# EEZ_PSU_power_board_r5B8.net
KiCad netlist of a schematic drawn in EAGLE
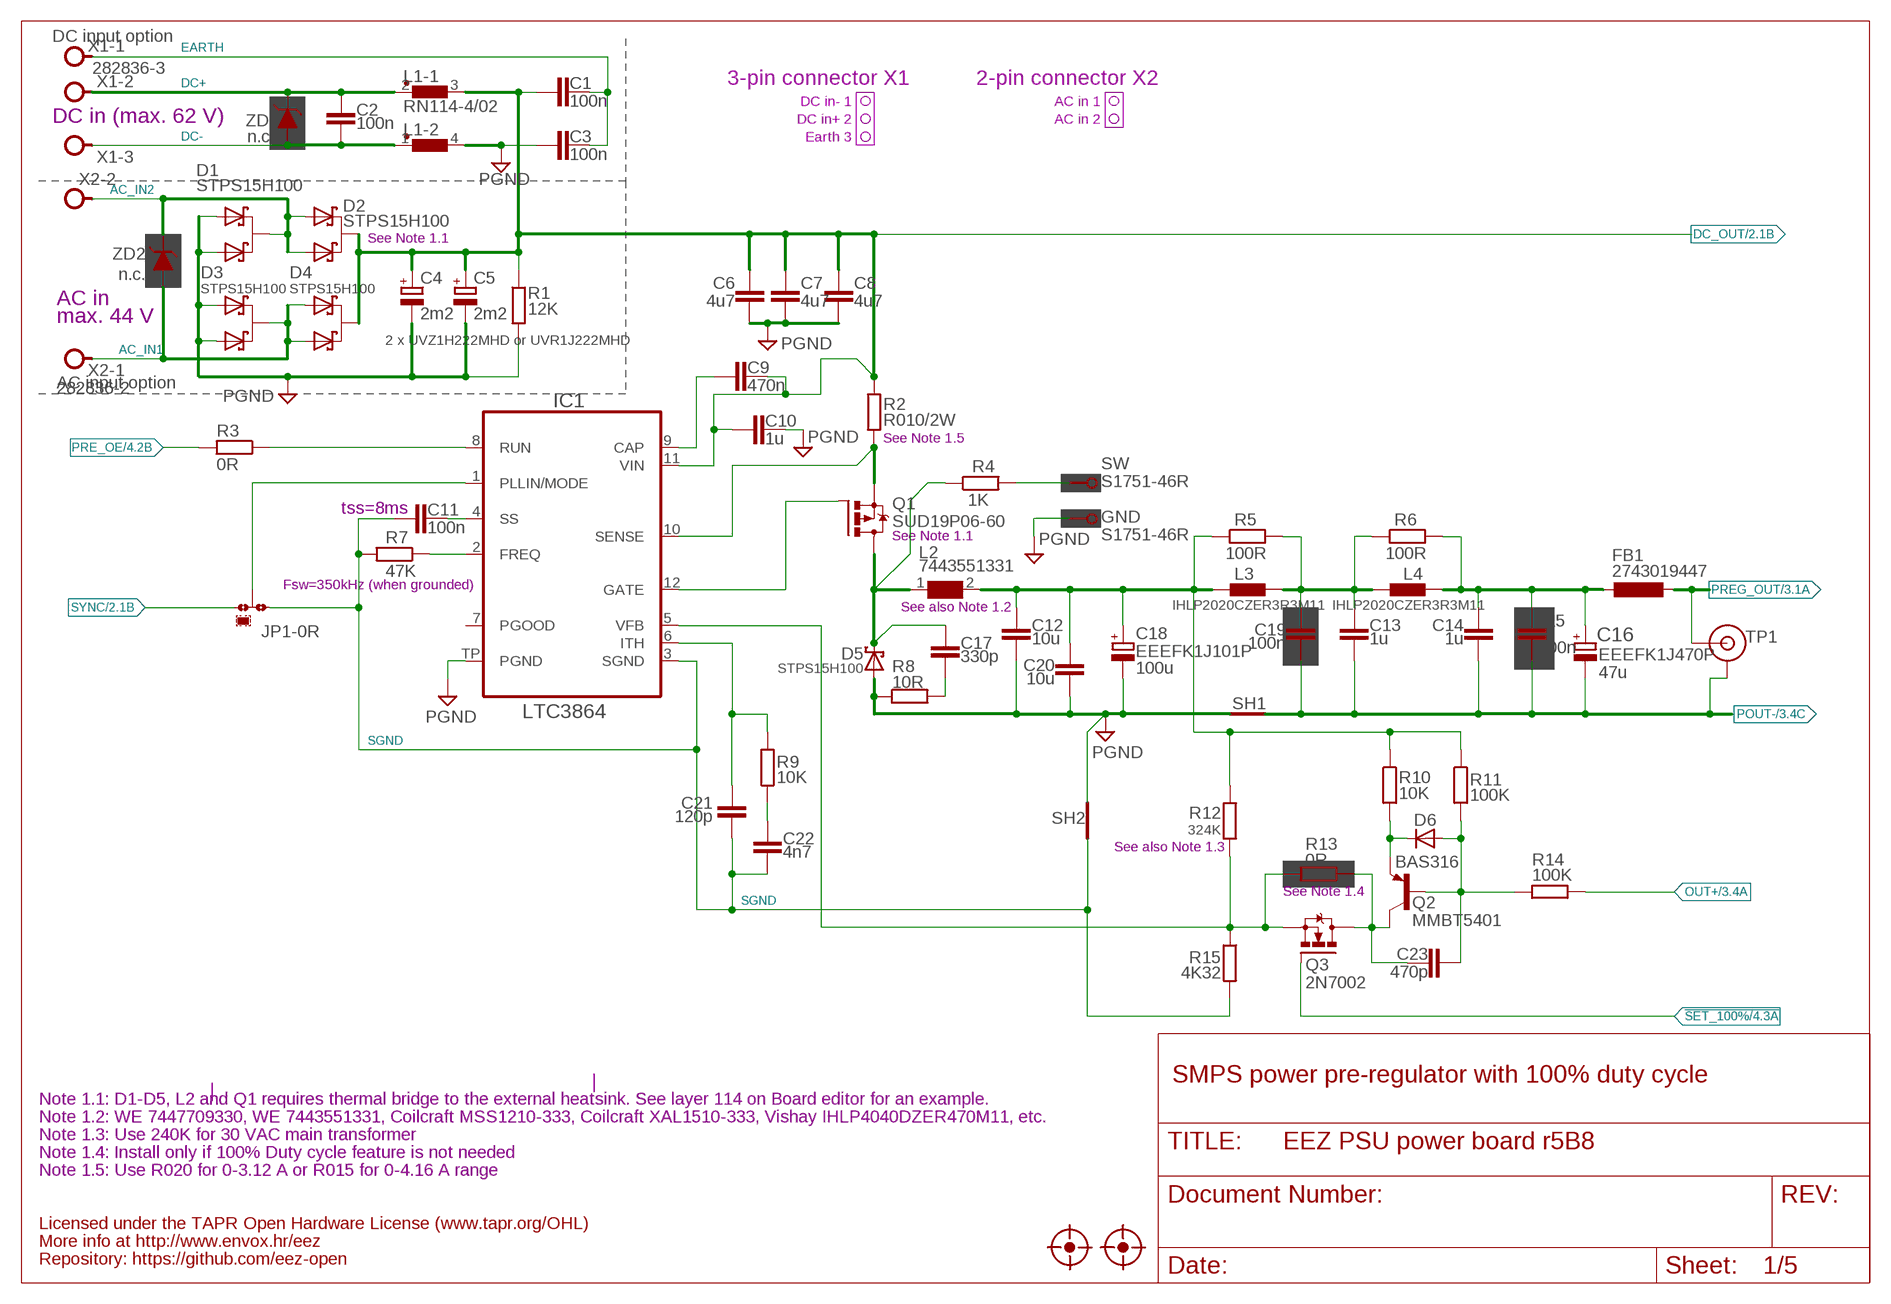
[diagram p0: schematic, sheet 1]
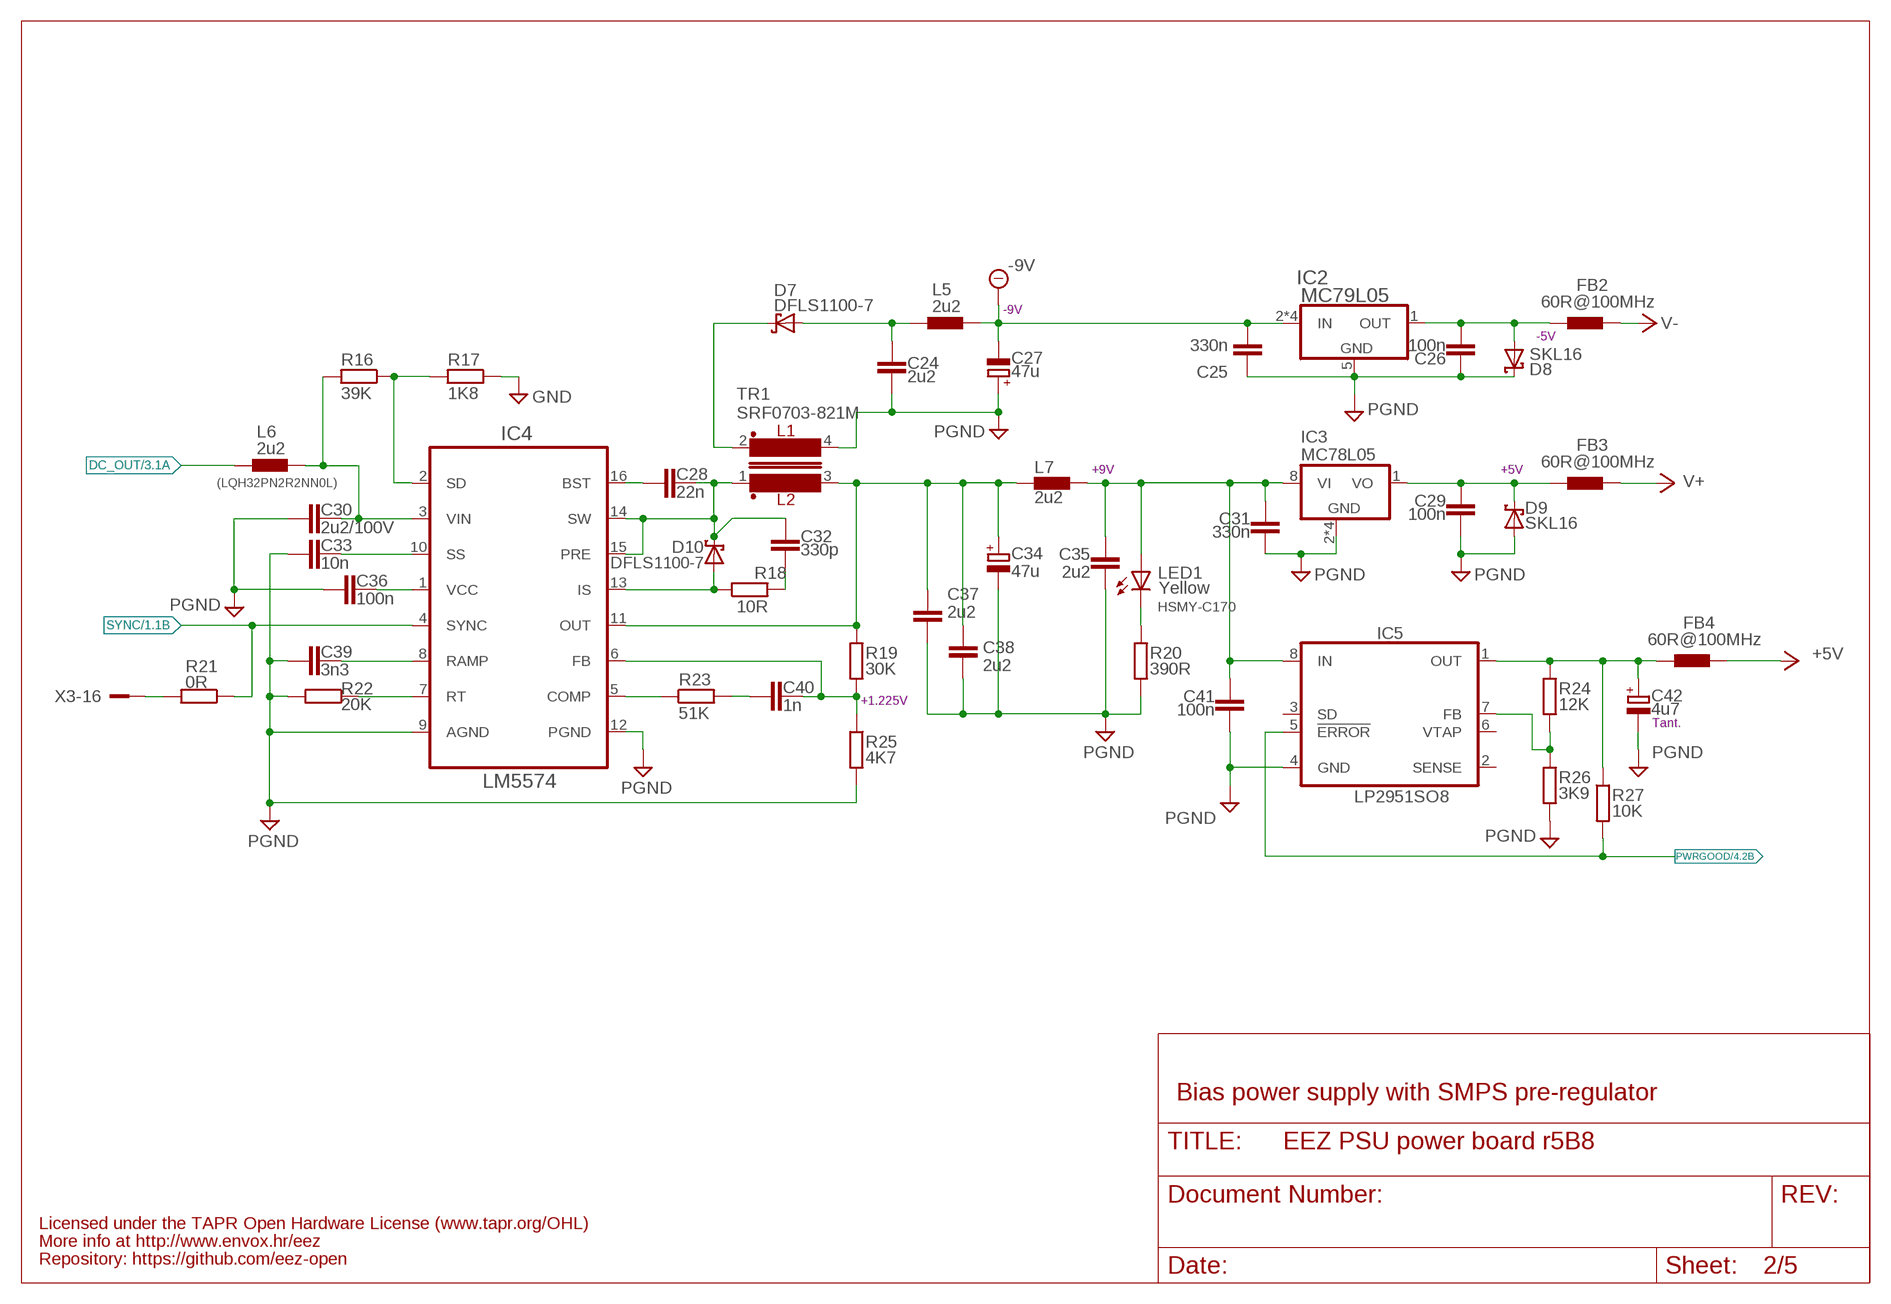
[diagram p1: schematic, sheet 2]
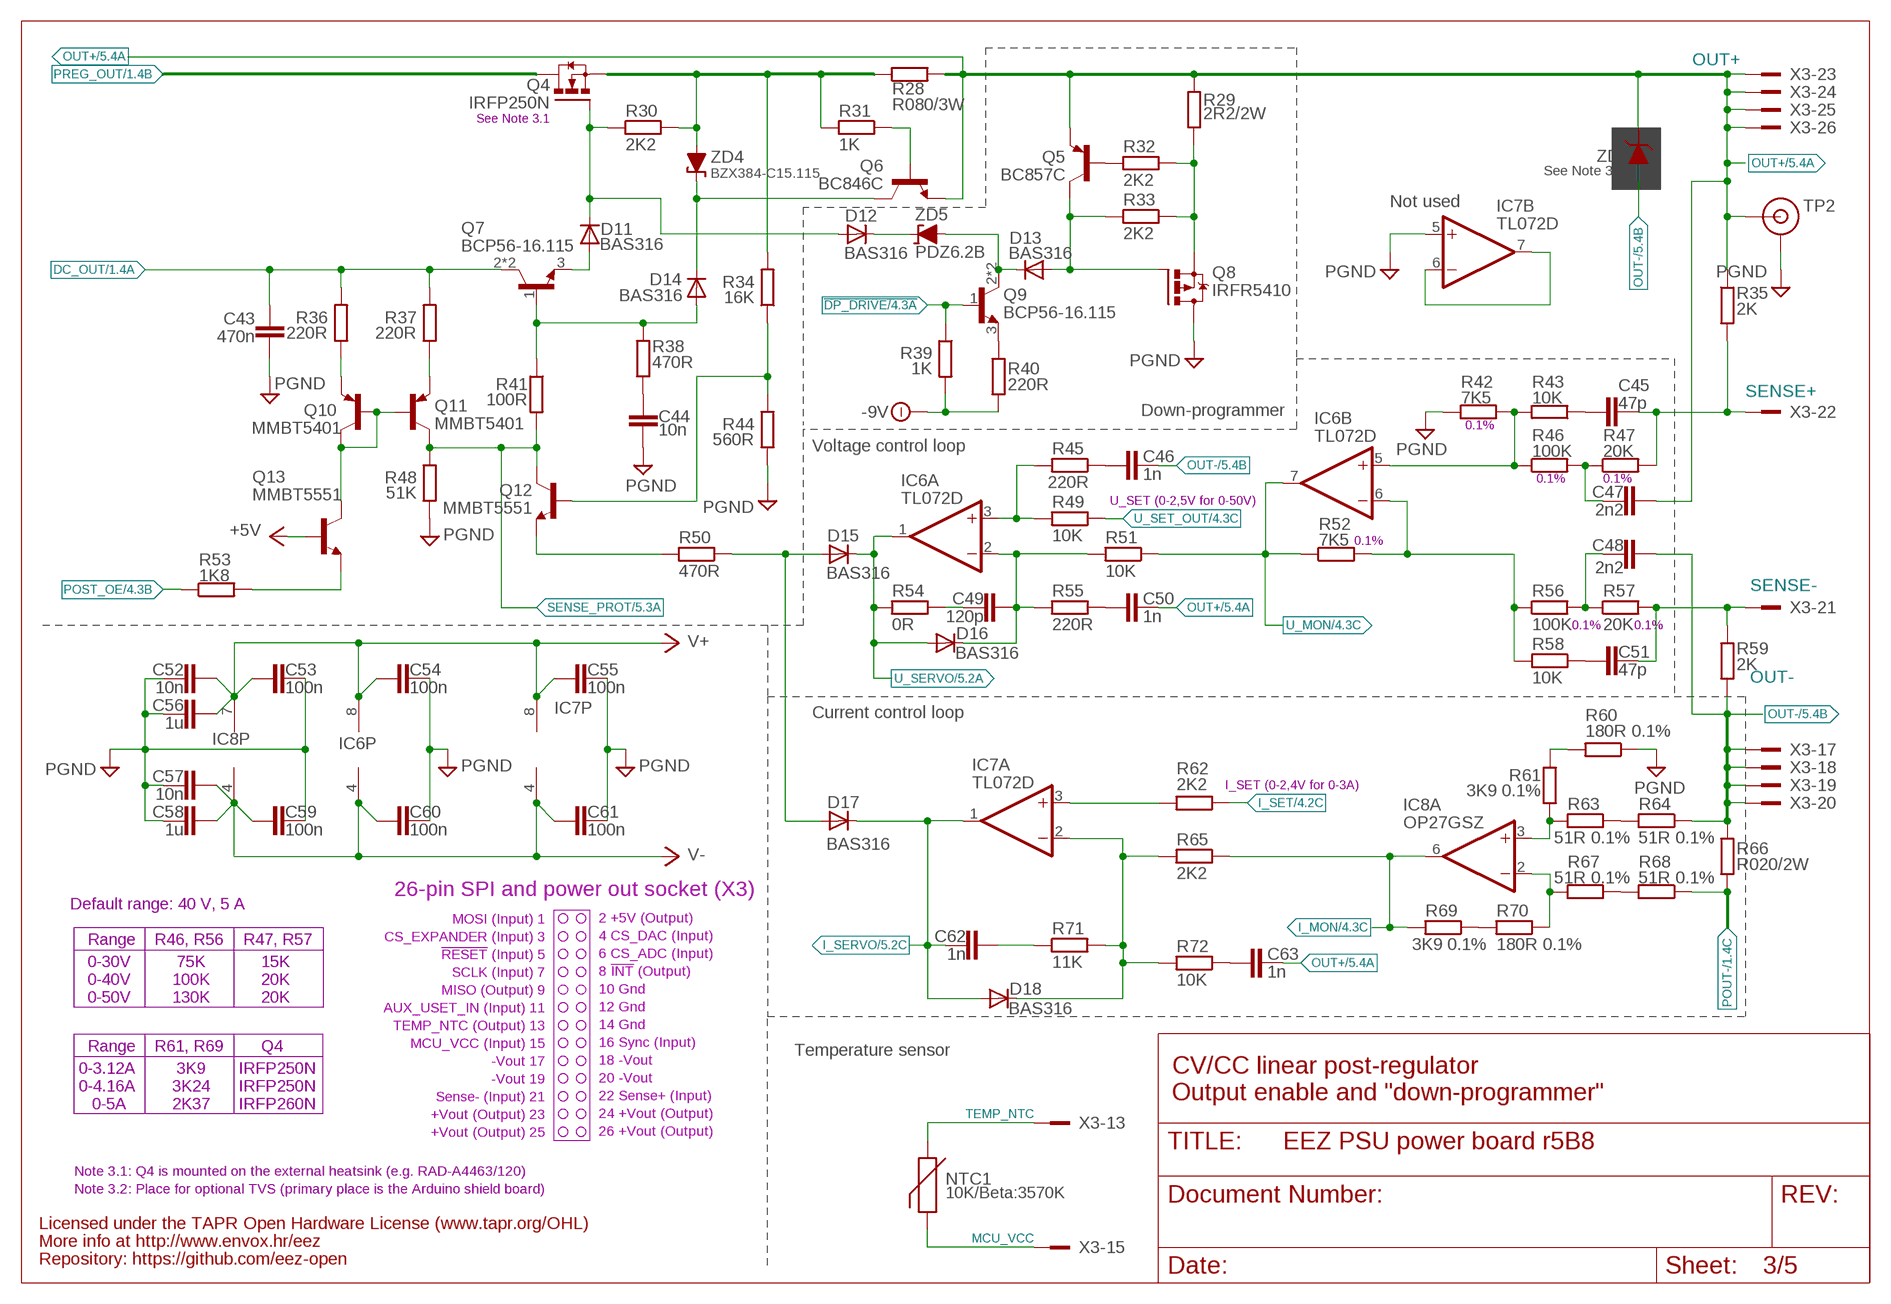
[diagram p2: schematic, sheet 3]
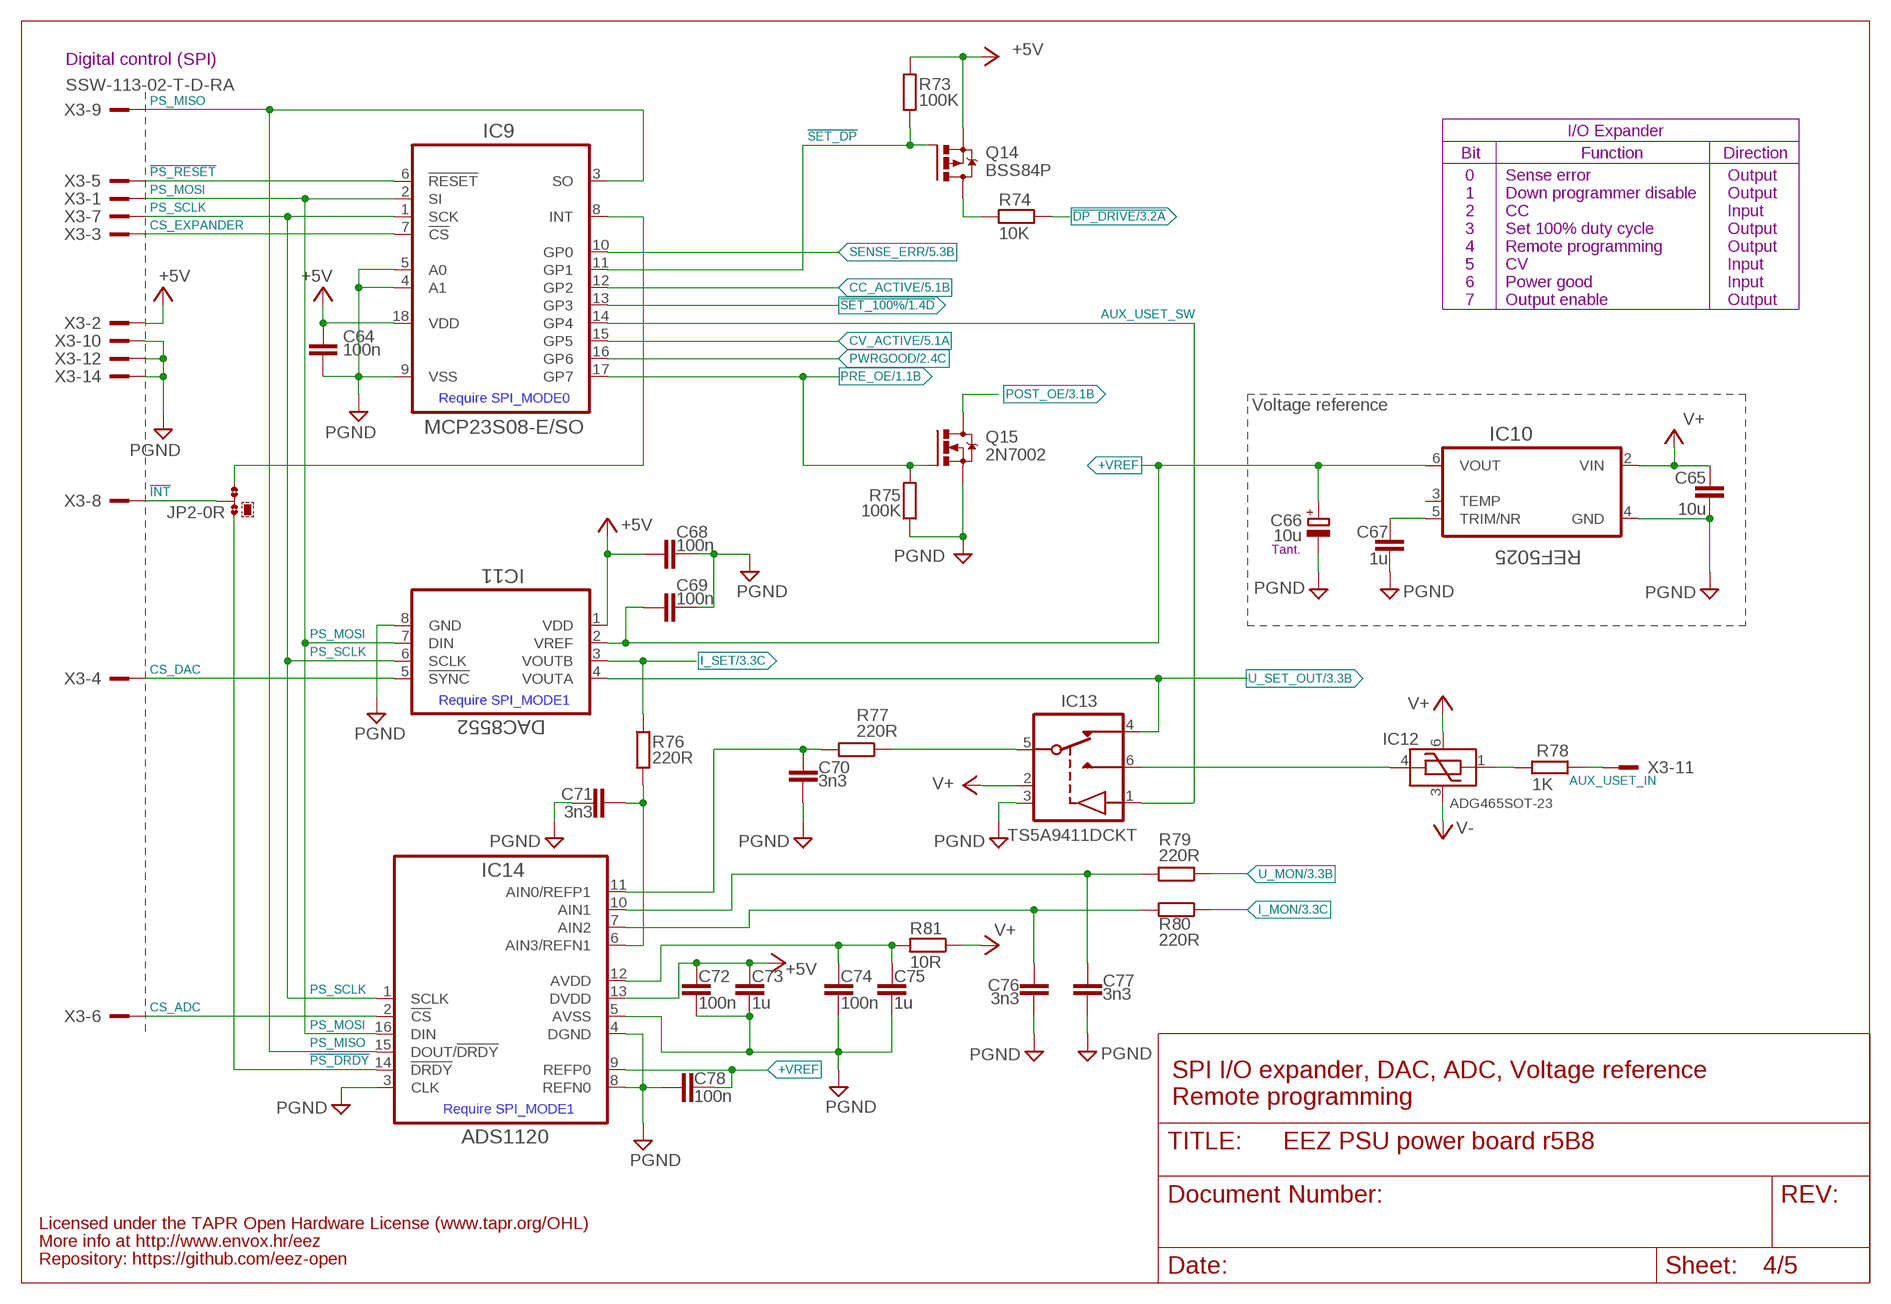
[diagram p3: schematic, sheet 4]
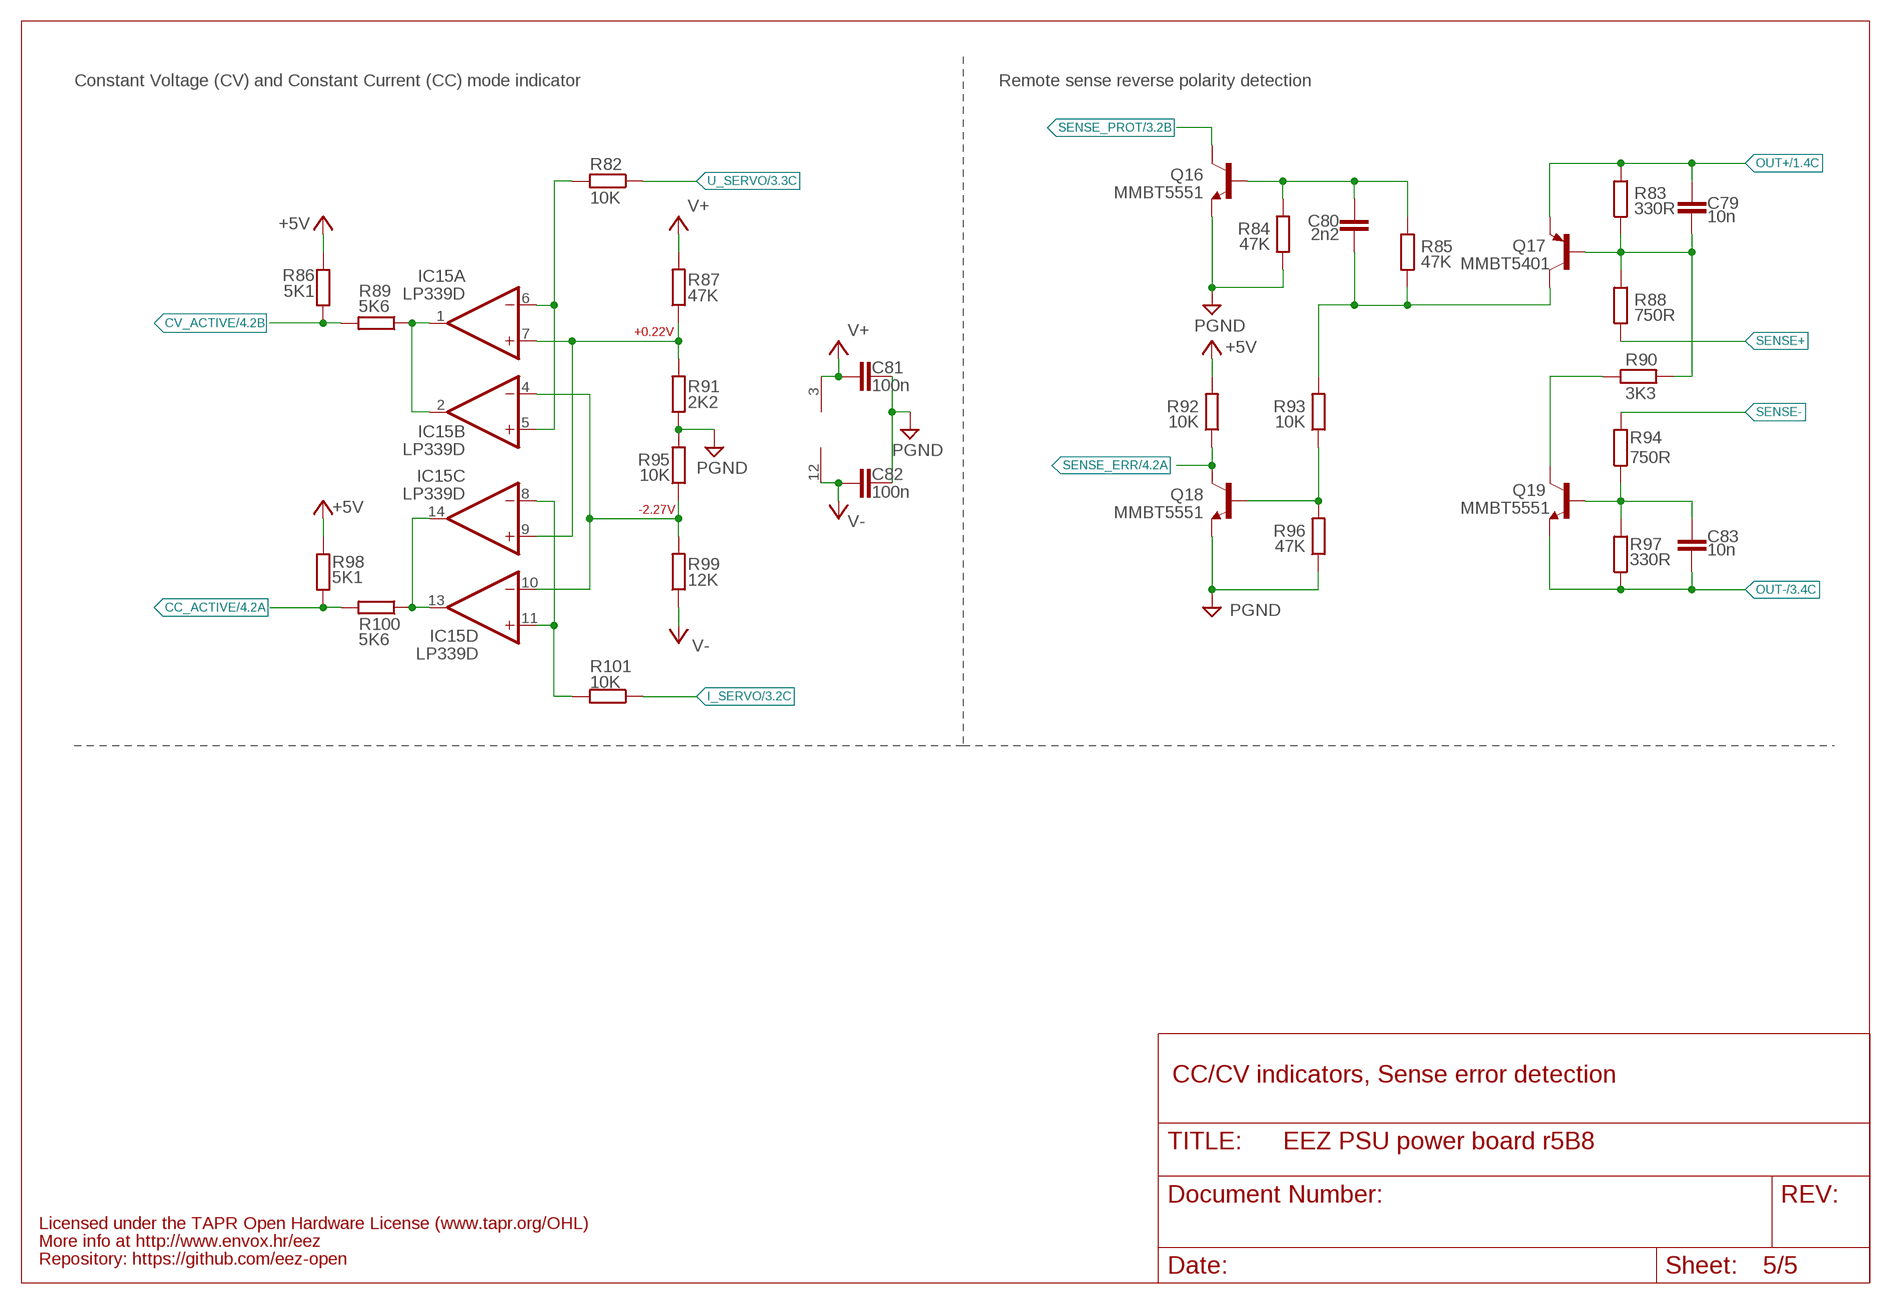
[diagram p4: schematic, sheet 5]

(export (version "E")
  (design (tool "Eeschema 10.0.6"))
  (components
    (comp (ref "C24")
      (value "2u2")
      (footprint "eagle-import:C0805")
      (libsource (lib "eagle-import") (part "C-EUC0805"))
    )
    (comp (ref "C25")
      (value "330n")
      (footprint "eagle-import:C0805")
      (libsource (lib "eagle-import") (part "C-EUC0805"))
    )
    (comp (ref "C26")
      (value "100n")
      (footprint "eagle-import:C0805")
      (libsource (lib "eagle-import") (part "C-EUC0805"))
    )
    (comp (ref "C27")
      (value "47u")
      (footprint "eagle-import:CAPAE660X610N")
      (libsource (lib "eagle-import") (part "ECAPPANASONIC_H"))
    )
    (comp (ref "C28")
      (value "22n")
      (footprint "eagle-import:C0805")
      (libsource (lib "eagle-import") (part "C-EUC0805"))
    )
    (comp (ref "C29")
      (value "100n")
      (footprint "eagle-import:C0805")
      (libsource (lib "eagle-import") (part "C-EUC0805"))
    )
    (comp (ref "C30")
      (value "2u2/100V")
      (footprint "eagle-import:C1210")
      (libsource (lib "eagle-import") (part "C-EUC1210"))
    )
    (comp (ref "C31")
      (value "330n")
      (footprint "eagle-import:C0805")
      (libsource (lib "eagle-import") (part "C-EUC0805"))
    )
    (comp (ref "C32")
      (value "330p")
      (footprint "eagle-import:C0805")
      (libsource (lib "eagle-import") (part "C-EUC0805"))
    )
    (comp (ref "C33")
      (value "10n")
      (footprint "eagle-import:C0805")
      (libsource (lib "eagle-import") (part "C-EUC0805"))
    )
    (comp (ref "C34")
      (value "47u")
      (footprint "eagle-import:CAPAE660X610N")
      (libsource (lib "eagle-import") (part "ECAPPANASONIC_H"))
    )
    (comp (ref "C35")
      (value "2u2")
      (footprint "eagle-import:C0805")
      (libsource (lib "eagle-import") (part "C-EUC0805"))
    )
    (comp (ref "C36")
      (value "100n")
      (footprint "eagle-import:C0805")
      (libsource (lib "eagle-import") (part "C-EUC0805"))
    )
    (comp (ref "C37")
      (value "2u2")
      (footprint "eagle-import:C0805")
      (libsource (lib "eagle-import") (part "C-EUC0805"))
    )
    (comp (ref "C38")
      (value "2u2")
      (footprint "eagle-import:C0805")
      (libsource (lib "eagle-import") (part "C-EUC0805"))
    )
    (comp (ref "C39")
      (value "3n3")
      (footprint "eagle-import:C0805")
      (libsource (lib "eagle-import") (part "C-EUC0805"))
    )
    (comp (ref "C40")
      (value "1n")
      (footprint "eagle-import:C0805")
      (libsource (lib "eagle-import") (part "C-EUC0805"))
    )
    (comp (ref "C41")
      (value "100n")
      (footprint "eagle-import:C0805")
      (libsource (lib "eagle-import") (part "C-EUC0805"))
    )
    (comp (ref "C42")
      (value "4u7")
      (footprint "eagle-import:EC1206")
      (libsource (lib "eagle-import") (part "ECAP1206"))
    )
    (comp (ref "D7")
      (value "DFLS1100-7")
      (footprint "eagle-import:SOD123")
      (libsource (lib "eagle-import") (part "SCHOTTKYSOD123"))
    )
    (comp (ref "D8")
      (value "SKL16")
      (footprint "eagle-import:SOD123")
      (libsource (lib "eagle-import") (part "SCHOTTKYSOD123"))
    )
    (comp (ref "D9")
      (value "SKL16")
      (footprint "eagle-import:SOD123")
      (libsource (lib "eagle-import") (part "SCHOTTKYSOD123"))
    )
    (comp (ref "D10")
      (value "DFLS1100-7")
      (footprint "eagle-import:SOD123")
      (libsource (lib "eagle-import") (part "SCHOTTKYSOD123"))
    )
    (comp (ref "FB2")
      (value "60R@100MHz")
      (footprint "eagle-import:BEAD0603")
      (libsource (lib "eagle-import") (part "FERRITE_BEAD0603"))
    )
    (comp (ref "FB3")
      (value "60R@100MHz")
      (footprint "eagle-import:BEAD0603")
      (libsource (lib "eagle-import") (part "FERRITE_BEAD0603"))
    )
    (comp (ref "FB4")
      (value "60R@100MHz")
      (footprint "eagle-import:BEAD0603")
      (libsource (lib "eagle-import") (part "FERRITE_BEAD0603"))
    )
    (comp (ref "IC2")
      (value "MC79L05")
      (footprint "eagle-import:SOIC127P600X173-8N")
      (libsource (lib "eagle-import") (part "MC79LXXSOIC"))
    )
    (comp (ref "IC3")
      (value "MC78L05")
      (footprint "eagle-import:SOIC127P600X173-8N")
      (libsource (lib "eagle-import") (part "MC78LXXSOIC8"))
    )
    (comp (ref "IC4")
      (value "LM5574")
      (footprint "eagle-import:SOP65P640X110-16N")
      (fields (field (name "MPN") "LM5574MT"))
      (libsource (lib "eagle-import") (part "LM5574"))
    )
    (comp (ref "IC5")
      (value "LP2951SO8")
      (footprint "eagle-import:SOIC127P600X175-8N")
      (libsource (lib "eagle-import") (part "LP2951SO8"))
    )
    (comp (ref "L5")
      (value "2u2")
      (footprint "eagle-import:L1210")
      (libsource (lib "eagle-import") (part "L1210"))
    )
    (comp (ref "L6")
      (value "2u2")
      (footprint "eagle-import:L1210")
      (libsource (lib "eagle-import") (part "L1210"))
    )
    (comp (ref "L7")
      (value "2u2")
      (footprint "eagle-import:L1210")
      (libsource (lib "eagle-import") (part "L1210"))
    )
    (comp (ref "LED1")
      (value "HSMY-C170")
      (footprint "eagle-import:LED_0805")
      (libsource (lib "eagle-import") (part "LED0805"))
    )
    (comp (ref "R16")
      (value "39K")
      (footprint "eagle-import:R0805")
      (libsource (lib "eagle-import") (part "R-EU_R0805"))
    )
    (comp (ref "R17")
      (value "1K8")
      (footprint "eagle-import:R0805")
      (libsource (lib "eagle-import") (part "R-EU_R0805"))
    )
    (comp (ref "R18")
      (value "10R")
      (footprint "eagle-import:R1206")
      (libsource (lib "eagle-import") (part "R-EU_R1206"))
    )
    (comp (ref "R19")
      (value "30K")
      (footprint "eagle-import:R0805")
      (libsource (lib "eagle-import") (part "R-EU_R0805"))
    )
    (comp (ref "R20")
      (value "390R")
      (footprint "eagle-import:R0805")
      (libsource (lib "eagle-import") (part "R-EU_R0805"))
    )
    (comp (ref "R21")
      (value "0R")
      (footprint "eagle-import:R0805")
      (libsource (lib "eagle-import") (part "R-EU_R0805"))
    )
    (comp (ref "R22")
      (value "20K")
      (footprint "eagle-import:R0805")
      (libsource (lib "eagle-import") (part "R-EU_R0805"))
    )
    (comp (ref "R23")
      (value "51K")
      (footprint "eagle-import:R0805")
      (libsource (lib "eagle-import") (part "R-EU_R0805"))
    )
    (comp (ref "R24")
      (value "12K")
      (footprint "eagle-import:R0805")
      (libsource (lib "eagle-import") (part "R-EU_R0805"))
    )
    (comp (ref "R25")
      (value "4K7")
      (footprint "eagle-import:R0805")
      (libsource (lib "eagle-import") (part "R-EU_R0805"))
    )
    (comp (ref "R26")
      (value "3K9")
      (footprint "eagle-import:R0805")
      (libsource (lib "eagle-import") (part "R-EU_R0805"))
    )
    (comp (ref "R27")
      (value "10K")
      (footprint "eagle-import:R0805")
      (libsource (lib "eagle-import") (part "R-EU_R0805"))
    )
    (comp (ref "TR1")
      (value "SRF0703-821M")
      (footprint "eagle-import:SRF0703")
      (libsource (lib "eagle-import") (part "BOURNS_SRF0703INV"))
    )
    (comp (ref "X3")
      (value "SSW-113-02-T-D-RA")
      (footprint "eagle-import:SSW-113-02-T-D-RA")
      (fields (field (name "FARNELL") "1805583"))
      (libsource (lib "eagle-import") (part "SSW-113-02-T-D-RA"))
    )
    (comp (ref "C1")
      (value "100n")
      (footprint "eagle-import:C1206")
      (libsource (lib "eagle-import") (part "C-EUC1206"))
    )
    (comp (ref "C2")
      (value "100n")
      (footprint "eagle-import:C1206")
      (libsource (lib "eagle-import") (part "C-EUC1206"))
    )
    (comp (ref "C3")
      (value "100n")
      (footprint "eagle-import:C1206")
      (libsource (lib "eagle-import") (part "C-EUC1206"))
    )
    (comp (ref "C4")
      (value "2m2")
      (footprint "eagle-import:ECAP7.5_18")
      (libsource (lib "eagle-import") (part "ECAP7.5G_18MM"))
    )
    (comp (ref "C5")
      (value "2m2")
      (footprint "eagle-import:ECAP7.5_18")
      (libsource (lib "eagle-import") (part "ECAP7.5G_18MM"))
    )
    (comp (ref "C6")
      (value "4u7")
      (footprint "eagle-import:C1210")
      (libsource (lib "eagle-import") (part "C-EUC1210"))
    )
    (comp (ref "C7")
      (value "4u7")
      (footprint "eagle-import:C1210")
      (libsource (lib "eagle-import") (part "C-EUC1210"))
    )
    (comp (ref "C8")
      (value "4u7")
      (footprint "eagle-import:C1210")
      (libsource (lib "eagle-import") (part "C-EUC1210"))
    )
    (comp (ref "C9")
      (value "470n")
      (footprint "eagle-import:C0805")
      (libsource (lib "eagle-import") (part "C-EUC0805"))
    )
    (comp (ref "C10")
      (value "1u")
      (footprint "eagle-import:C1206")
      (libsource (lib "eagle-import") (part "C-EUC1206"))
    )
    (comp (ref "C11")
      (value "100n")
      (footprint "eagle-import:C0805")
      (libsource (lib "eagle-import") (part "C-EUC0805"))
    )
    (comp (ref "C12")
      (value "10u")
      (footprint "eagle-import:C1210")
      (libsource (lib "eagle-import") (part "C-EUC1210"))
    )
    (comp (ref "C13")
      (value "1u")
      (footprint "eagle-import:C1206")
      (libsource (lib "eagle-import") (part "resistor_C-EUC1206"))
    )
    (comp (ref "C14")
      (value "1u")
      (footprint "eagle-import:C1206")
      (libsource (lib "eagle-import") (part "resistor_C-EUC1206"))
    )
    (comp (ref "C15")
      (value "100n")
      (footprint "eagle-import:C0805")
      (libsource (lib "eagle-import") (part "C-EUC0805"))
    )
    (comp (ref "C16")
      (value "EEEFK1J470P")
      (footprint "eagle-import:CAPAE830X1050N")
      (fields (field (name "MPN") "EEE-FK1J470P") (field (name "TOLERANCE") "±20 %"))
      (libsource (lib "eagle-import") (part "EEE--CASE-FFK1J470P"))
    )
    (comp (ref "C17")
      (value "330p")
      (footprint "eagle-import:C0805")
      (libsource (lib "eagle-import") (part "C-EUC0805"))
    )
    (comp (ref "C18")
      (value "EEEFK1J101P")
      (footprint "eagle-import:PANASONIC_F")
      (libsource (lib "eagle-import") (part "ECAPF"))
    )
    (comp (ref "C19")
      (value "100n")
      (footprint "eagle-import:C0805")
      (libsource (lib "eagle-import") (part "C-EUC0805"))
    )
    (comp (ref "C20")
      (value "10u")
      (footprint "eagle-import:C1210")
      (libsource (lib "eagle-import") (part "C-EUC1210"))
    )
    (comp (ref "C21")
      (value "120p")
      (footprint "eagle-import:C0805")
      (libsource (lib "eagle-import") (part "C-EUC0805"))
    )
    (comp (ref "C22")
      (value "4n7")
      (footprint "eagle-import:C0805")
      (libsource (lib "eagle-import") (part "C-EUC0805"))
    )
    (comp (ref "C23")
      (value "470p")
      (footprint "eagle-import:C0805")
      (libsource (lib "eagle-import") (part "C-EUC0805"))
    )
    (comp (ref "D1")
      (value "STPS15H100")
      (footprint "eagle-import:TO252@1")
      (libsource (lib "eagle-import") (part "VS-6CWQ06FNPBF"))
    )
    (comp (ref "D2")
      (value "STPS15H100")
      (footprint "eagle-import:TO252@1")
      (libsource (lib "eagle-import") (part "VS-6CWQ06FNPBF"))
    )
    (comp (ref "D3")
      (value "STPS15H100")
      (footprint "eagle-import:TO252@1")
      (libsource (lib "eagle-import") (part "VS-6CWQ06FNPBF"))
    )
    (comp (ref "D4")
      (value "STPS15H100")
      (footprint "eagle-import:TO252@1")
      (libsource (lib "eagle-import") (part "VS-6CWQ06FNPBF"))
    )
    (comp (ref "D5")
      (value "STPS15H100")
      (footprint "eagle-import:TO252")
      (libsource (lib "eagle-import") (part "SCHOTTKYTO252"))
    )
    (comp (ref "D6")
      (value "BAS316")
      (footprint "eagle-import:SOD323-W")
      (libsource (lib "eagle-import") (part "DIODE-SOD323-W"))
    )
    (comp (ref "FB1")
      (value "2743019447")
      (footprint "eagle-import:L1812")
      (libsource (lib "eagle-import") (part "L-EUL1812"))
    )
    (comp (ref "GND")
      (value "S1751-46R")
      (footprint "eagle-import:S1751-46R")
      (libsource (lib "eagle-import") (part "PCB_TEST_TABSMD"))
    )
    (comp (ref "IC1")
      (value "LTC3864")
      (footprint "eagle-import:LTC_05-08-1666")
      (libsource (lib "eagle-import") (part "LTC3864"))
    )
    (comp (ref "JP1")
      (value "0R-JUMPA")
      (footprint "eagle-import:A0R-JMP")
      (libsource (lib "eagle-import") (part "0R-JUMPA"))
    )
    (comp (ref "L1")
      (value "RN114-4/02")
      (footprint "eagle-import:RN114")
      (libsource (lib "eagle-import") (part "RN114"))
    )
    (comp (ref "L2")
      (value "7443551331")
      (footprint "eagle-import:WE-HCI_1350_1365")
      (libsource (lib "eagle-import") (part "WE-HCI_1350/1365-7443551331"))
    )
    (comp (ref "L3")
      (value "IHLP2020CZER3R3M11")
      (footprint "eagle-import:IHLP-2020BZ-11")
      (libsource (lib "eagle-import") (part "IHLP-2020BZ-11"))
    )
    (comp (ref "L4")
      (value "IHLP2020CZER3R3M11")
      (footprint "eagle-import:IHLP-2020BZ-11")
      (libsource (lib "eagle-import") (part "IHLP-2020BZ-11"))
    )
    (comp (ref "Q1")
      (value "SUD19P06-60")
      (footprint "eagle-import:TO229P990X239-3N")
      (libsource (lib "eagle-import") (part "P-MOSFETDPAK"))
    )
    (comp (ref "Q2")
      (value "MMBT5401")
      (footprint "eagle-import:SOT23-BEC")
      (libsource (lib "eagle-import") (part "-PNP-SOT23-BECBC857B"))
    )
    (comp (ref "Q3")
      (value "2N7002")
      (footprint "eagle-import:SOT103P240X110-3N")
      (fields (field (name "MPN") "2N7002-7-F"))
      (libsource (lib "eagle-import") (part "2N7002"))
    )
    (comp (ref "R1")
      (value "12K")
      (footprint "eagle-import:R1206")
      (libsource (lib "eagle-import") (part "R-EU_R1206"))
    )
    (comp (ref "R2")
      (value "R010/2W")
      (footprint "eagle-import:R2512")
      (libsource (lib "eagle-import") (part "R-EU_R2512"))
    )
    (comp (ref "R3")
      (value "0R")
      (footprint "eagle-import:R0805")
      (libsource (lib "eagle-import") (part "R-EU_R0805"))
    )
    (comp (ref "R4")
      (value "1K")
      (footprint "eagle-import:R0805")
      (libsource (lib "eagle-import") (part "R-EU_R0805"))
    )
    (comp (ref "R5")
      (value "100R")
      (footprint "eagle-import:R0805")
      (libsource (lib "eagle-import") (part "R-EU_R0805"))
    )
    (comp (ref "R6")
      (value "100R")
      (footprint "eagle-import:R0805")
      (libsource (lib "eagle-import") (part "R-EU_R0805"))
    )
    (comp (ref "R7")
      (value "47K")
      (footprint "eagle-import:R0805")
      (libsource (lib "eagle-import") (part "R-EU_R0805"))
    )
    (comp (ref "R8")
      (value "10R")
      (footprint "eagle-import:R1206")
      (libsource (lib "eagle-import") (part "R-EU_R1206"))
    )
    (comp (ref "R9")
      (value "10K")
      (footprint "eagle-import:R0805")
      (libsource (lib "eagle-import") (part "R-EU_R0805"))
    )
    (comp (ref "R10")
      (value "10K")
      (footprint "eagle-import:R0805")
      (libsource (lib "eagle-import") (part "R-EU_R0805"))
    )
    (comp (ref "R11")
      (value "100K")
      (footprint "eagle-import:R0805")
      (libsource (lib "eagle-import") (part "R-EU_R0805"))
    )
    (comp (ref "R12")
      (value "324K")
      (footprint "eagle-import:R0805")
      (libsource (lib "eagle-import") (part "R-EU_R0805"))
    )
    (comp (ref "R13")
      (value "0R")
      (footprint "eagle-import:R0805")
      (libsource (lib "eagle-import") (part "R-EU_R0805"))
    )
    (comp (ref "R14")
      (value "100K")
      (footprint "eagle-import:R0805")
      (libsource (lib "eagle-import") (part "R-EU_R0805"))
    )
    (comp (ref "R15")
      (value "4K32")
      (footprint "eagle-import:R0805")
      (libsource (lib "eagle-import") (part "R-EU_R0805"))
    )
    (comp (ref "SH1")
      (value "Pgnd to Pout- short")
      (footprint "eagle-import:SHORT_NOHOLE")
      (libsource (lib "eagle-import") (part "SHORTNOHOLE"))
    )
    (comp (ref "SH2")
      (value "Sgnd to Pgnd short")
      (footprint "eagle-import:SHORT_NOHOLE")
      (libsource (lib "eagle-import") (part "SHORTNOHOLE"))
    )
    (comp (ref "SW")
      (value "S1751-46R")
      (footprint "eagle-import:S1751-46R")
      (libsource (lib "eagle-import") (part "PCB_TEST_TABSMD"))
    )
    (comp (ref "TP1")
      (value "TEST_POINT")
      (footprint "eagle-import:TP_1.1MM")
      (libsource (lib "eagle-import") (part "TEST_POINT"))
    )
    (comp (ref "U$11")
      (value "FIDUCIAL_2")
      (footprint "eagle-import:FIDUCIAL_DUAL")
      (libsource (lib "eagle-import") (part "FIDUCIAL_2"))
    )
    (comp (ref "U$12")
      (value "FIDUCIAL_2")
      (footprint "eagle-import:FIDUCIAL_DUAL")
      (libsource (lib "eagle-import") (part "FIDUCIAL_2"))
    )
    (comp (ref "X1")
      (value "282836-3")
      (footprint "eagle-import:TBLOCK5.0_3")
      (libsource (lib "eagle-import") (part "TBLOCK5.0_3A"))
    )
    (comp (ref "X2")
      (value "282836-2")
      (footprint "eagle-import:TBLOCK5.0_2")
      (libsource (lib "eagle-import") (part "TBLOCK5.0_2A"))
    )
    (comp (ref "ZD1")
      (value "n.c.")
      (footprint "eagle-import:DO214AA")
      (libsource (lib "eagle-import") (part "P6SMB68A"))
    )
    (comp (ref "ZD2")
      (value "n.c.")
      (footprint "eagle-import:DO214AA")
      (libsource (lib "eagle-import") (part "P6SMB68A"))
    )
    (comp (ref "C43")
      (value "470n")
      (footprint "eagle-import:C1812")
      (libsource (lib "eagle-import") (part "C-EUC1812"))
    )
    (comp (ref "C44")
      (value "10n")
      (footprint "eagle-import:C0805")
      (libsource (lib "eagle-import") (part "C-EUC0805"))
    )
    (comp (ref "C45")
      (value "47p")
      (footprint "eagle-import:C0805")
      (libsource (lib "eagle-import") (part "C-EUC0805"))
    )
    (comp (ref "C46")
      (value "1n")
      (footprint "eagle-import:C0805")
      (libsource (lib "eagle-import") (part "C-EUC0805"))
    )
    (comp (ref "C47")
      (value "2n2")
      (footprint "eagle-import:C0805")
      (libsource (lib "eagle-import") (part "C-EUC0805"))
    )
    (comp (ref "C48")
      (value "2n2")
      (footprint "eagle-import:C0805")
      (libsource (lib "eagle-import") (part "C-EUC0805"))
    )
    (comp (ref "C49")
      (value "120p")
      (footprint "eagle-import:C0805")
      (libsource (lib "eagle-import") (part "C-EUC0805"))
    )
    (comp (ref "C50")
      (value "1n")
      (footprint "eagle-import:C0805")
      (libsource (lib "eagle-import") (part "C-EUC0805"))
    )
    (comp (ref "C51")
      (value "47p")
      (footprint "eagle-import:C0805")
      (libsource (lib "eagle-import") (part "C-EUC0805"))
    )
    (comp (ref "C52")
      (value "10n")
      (footprint "eagle-import:C0805")
      (libsource (lib "eagle-import") (part "C-EUC0805"))
    )
    (comp (ref "C53")
      (value "100n")
      (footprint "eagle-import:C0603")
      (libsource (lib "eagle-import") (part "C-EUC0603"))
    )
    (comp (ref "C54")
      (value "100n")
      (footprint "eagle-import:C0603")
      (libsource (lib "eagle-import") (part "C-EUC0603"))
    )
    (comp (ref "C55")
      (value "100n")
      (footprint "eagle-import:C0603")
      (libsource (lib "eagle-import") (part "C-EUC0603"))
    )
    (comp (ref "C56")
      (value "1u")
      (footprint "eagle-import:C0805")
      (libsource (lib "eagle-import") (part "C-EUC0805"))
    )
    (comp (ref "C57")
      (value "10n")
      (footprint "eagle-import:C0805")
      (libsource (lib "eagle-import") (part "C-EUC0805"))
    )
    (comp (ref "C58")
      (value "1u")
      (footprint "eagle-import:C0805")
      (libsource (lib "eagle-import") (part "C-EUC0805"))
    )
    (comp (ref "C59")
      (value "100n")
      (footprint "eagle-import:C0603")
      (libsource (lib "eagle-import") (part "C-EUC0603"))
    )
    (comp (ref "C60")
      (value "100n")
      (footprint "eagle-import:C0603")
      (libsource (lib "eagle-import") (part "C-EUC0603"))
    )
    (comp (ref "C61")
      (value "100n")
      (footprint "eagle-import:C0603")
      (libsource (lib "eagle-import") (part "C-EUC0603"))
    )
    (comp (ref "C62")
      (value "1n")
      (footprint "eagle-import:C0805")
      (libsource (lib "eagle-import") (part "C-EUC0805"))
    )
    (comp (ref "C63")
      (value "1n")
      (footprint "eagle-import:C0805")
      (libsource (lib "eagle-import") (part "C-EUC0805"))
    )
    (comp (ref "D11")
      (value "BAS316")
      (footprint "eagle-import:SOD323-W")
      (libsource (lib "eagle-import") (part "DIODE-SOD323-W"))
    )
    (comp (ref "D12")
      (value "BAS316")
      (footprint "eagle-import:SOD323-W")
      (libsource (lib "eagle-import") (part "DIODE-SOD323-W"))
    )
    (comp (ref "D13")
      (value "BAS316")
      (footprint "eagle-import:SOD323-W")
      (libsource (lib "eagle-import") (part "DIODE-SOD323-W"))
    )
    (comp (ref "D14")
      (value "BAS316")
      (footprint "eagle-import:SOD323-W")
      (libsource (lib "eagle-import") (part "DIODE-SOD323-W"))
    )
    (comp (ref "D15")
      (value "BAS316")
      (footprint "eagle-import:SOD323-W")
      (libsource (lib "eagle-import") (part "DIODE-SOD323-W"))
    )
    (comp (ref "D16")
      (value "BAS316")
      (footprint "eagle-import:SOD323-W")
      (libsource (lib "eagle-import") (part "DIODE-SOD323-W"))
    )
    (comp (ref "D17")
      (value "BAS316")
      (footprint "eagle-import:SOD323-W")
      (libsource (lib "eagle-import") (part "DIODE-SOD323-W"))
    )
    (comp (ref "D18")
      (value "BAS316")
      (footprint "eagle-import:SOD323-W")
      (libsource (lib "eagle-import") (part "DIODE-SOD323-W"))
    )
    (comp (ref "IC6")
      (value "TL072D")
      (footprint "eagle-import:SOIC127P600X173-8N")
      (libsource (lib "eagle-import") (part "TL072SOIC8"))
    )
    (comp (ref "IC7")
      (value "TL072D")
      (footprint "eagle-import:SOIC127P600X173-8N")
      (libsource (lib "eagle-import") (part "TL072SOIC8"))
    )
    (comp (ref "IC8")
      (value "OP27GSZ")
      (footprint "eagle-import:SOIC127P600X173-8N")
      (libsource (lib "eagle-import") (part "OP27GSZSO8"))
    )
    (comp (ref "NTC1")
      (value "10K/Beta:3570K")
      (footprint "eagle-import:R_0204_5+0805")
      (libsource (lib "eagle-import") (part "NTC0805"))
    )
    (comp (ref "Q4")
      (value "IRFP250N")
      (footprint "eagle-import:TO247BH-CLR")
      (libsource (lib "eagle-import") (part "IRFP240BOTTOM"))
    )
    (comp (ref "Q5")
      (value "BC857C")
      (footprint "eagle-import:SOT23-BEC")
      (libsource (lib "eagle-import") (part "-PNP-SOT23-BECBC857C"))
    )
    (comp (ref "Q6")
      (value "BC846C")
      (footprint "eagle-import:SOT23-BEC")
      (libsource (lib "eagle-import") (part "-NPN-SOT23-BECBC846B"))
    )
    (comp (ref "Q7")
      (value "BCP56-16.115")
      (footprint "eagle-import:SOT230P700X180-4N")
      (libsource (lib "eagle-import") (part "BCP56"))
    )
    (comp (ref "Q8")
      (value "IRFR5410")
      (footprint "eagle-import:TO229P990X239-3N")
      (libsource (lib "eagle-import") (part "P-MOSFETDPAK"))
    )
    (comp (ref "Q9")
      (value "BCP56-16.115")
      (footprint "eagle-import:SOT230P700X180-4N")
      (libsource (lib "eagle-import") (part "BCP56"))
    )
    (comp (ref "Q10")
      (value "MMBT5401")
      (footprint "eagle-import:SOT23-BEC")
      (libsource (lib "eagle-import") (part "-PNP-SOT23-BECBC857B"))
    )
    (comp (ref "Q11")
      (value "MMBT5401")
      (footprint "eagle-import:SOT23-BEC")
      (libsource (lib "eagle-import") (part "-PNP-SOT23-BECBC857B"))
    )
    (comp (ref "Q12")
      (value "MMBT5551")
      (footprint "eagle-import:SOT23-BEC")
      (libsource (lib "eagle-import") (part "-NPN-SOT23-BECMMBT5551LT1"))
    )
    (comp (ref "Q13")
      (value "MMBT5551")
      (footprint "eagle-import:SOT23-BEC")
      (libsource (lib "eagle-import") (part "-NPN-SOT23-BECMMBT5551LT1"))
    )
    (comp (ref "R28")
      (value "R080/3W")
      (footprint "eagle-import:R2512")
      (libsource (lib "eagle-import") (part "R-EU_R2512"))
    )
    (comp (ref "R29")
      (value "2R2/2W")
      (footprint "eagle-import:R2512")
      (libsource (lib "eagle-import") (part "R-EU_R2512"))
    )
    (comp (ref "R30")
      (value "2K2")
      (footprint "eagle-import:R0805")
      (libsource (lib "eagle-import") (part "R-EU_R0805"))
    )
    (comp (ref "R31")
      (value "1K")
      (footprint "eagle-import:R0805")
      (libsource (lib "eagle-import") (part "R-EU_R0805"))
    )
    (comp (ref "R32")
      (value "2K2")
      (footprint "eagle-import:R0805")
      (libsource (lib "eagle-import") (part "R-EU_R0805"))
    )
    (comp (ref "R33")
      (value "2K2")
      (footprint "eagle-import:R0805")
      (libsource (lib "eagle-import") (part "R-EU_R0805"))
    )
    (comp (ref "R34")
      (value "16K")
      (footprint "eagle-import:R0805")
      (libsource (lib "eagle-import") (part "R-EU_R0805"))
    )
    (comp (ref "R35")
      (value "2K")
      (footprint "eagle-import:R0805")
      (libsource (lib "eagle-import") (part "R-EU_R0805"))
    )
    (comp (ref "R36")
      (value "220R")
      (footprint "eagle-import:R0805")
      (libsource (lib "eagle-import") (part "R-EU_R0805"))
    )
    (comp (ref "R37")
      (value "220R")
      (footprint "eagle-import:R0805")
      (libsource (lib "eagle-import") (part "R-EU_R0805"))
    )
    (comp (ref "R38")
      (value "470R")
      (footprint "eagle-import:R0805")
      (libsource (lib "eagle-import") (part "R-EU_R0805"))
    )
    (comp (ref "R39")
      (value "1K")
      (footprint "eagle-import:R0805")
      (libsource (lib "eagle-import") (part "R-EU_R0805"))
    )
    (comp (ref "R40")
      (value "220R")
      (footprint "eagle-import:R0805")
      (libsource (lib "eagle-import") (part "R-EU_R0805"))
    )
    (comp (ref "R41")
      (value "100R")
      (footprint "eagle-import:R0805")
      (libsource (lib "eagle-import") (part "R-EU_R0805"))
    )
    (comp (ref "R42")
      (value "7K5")
      (footprint "eagle-import:R0805")
      (libsource (lib "eagle-import") (part "R-EU_R0805"))
    )
    (comp (ref "R43")
      (value "10K")
      (footprint "eagle-import:R0805")
      (libsource (lib "eagle-import") (part "R-EU_R0805"))
    )
    (comp (ref "R44")
      (value "560R")
      (footprint "eagle-import:R0805")
      (libsource (lib "eagle-import") (part "R-EU_R0805"))
    )
    (comp (ref "R45")
      (value "220R")
      (footprint "eagle-import:R0805")
      (libsource (lib "eagle-import") (part "R-EU_R0805"))
    )
    (comp (ref "R46")
      (value "100K")
      (footprint "eagle-import:R0805")
      (libsource (lib "eagle-import") (part "R-EU_R0805"))
    )
    (comp (ref "R47")
      (value "20K")
      (footprint "eagle-import:R0805")
      (libsource (lib "eagle-import") (part "R-EU_R0805"))
    )
    (comp (ref "R48")
      (value "51K")
      (footprint "eagle-import:R0805")
      (libsource (lib "eagle-import") (part "R-EU_R0805"))
    )
    (comp (ref "R49")
      (value "10K")
      (footprint "eagle-import:R0805")
      (libsource (lib "eagle-import") (part "R-EU_R0805"))
    )
    (comp (ref "R50")
      (value "470R")
      (footprint "eagle-import:R0805")
      (libsource (lib "eagle-import") (part "R-EU_R0805"))
    )
    (comp (ref "R51")
      (value "10K")
      (footprint "eagle-import:R0805")
      (libsource (lib "eagle-import") (part "R-EU_R0805"))
    )
    (comp (ref "R52")
      (value "7K5")
      (footprint "eagle-import:R0805")
      (libsource (lib "eagle-import") (part "R-EU_R0805"))
    )
    (comp (ref "R53")
      (value "1K8")
      (footprint "eagle-import:R0805")
      (libsource (lib "eagle-import") (part "R-EU_R0805"))
    )
    (comp (ref "R54")
      (value "0R")
      (footprint "eagle-import:R0805")
      (libsource (lib "eagle-import") (part "R-EU_R0805"))
    )
    (comp (ref "R55")
      (value "220R")
      (footprint "eagle-import:R0805")
      (libsource (lib "eagle-import") (part "R-EU_R0805"))
    )
    (comp (ref "R56")
      (value "100K")
      (footprint "eagle-import:R0805")
      (libsource (lib "eagle-import") (part "R-EU_R0805"))
    )
    (comp (ref "R57")
      (value "20K")
      (footprint "eagle-import:R0805")
      (libsource (lib "eagle-import") (part "R-EU_R0805"))
    )
    (comp (ref "R58")
      (value "10K")
      (footprint "eagle-import:R0805")
      (libsource (lib "eagle-import") (part "R-EU_R0805"))
    )
    (comp (ref "R59")
      (value "2K")
      (footprint "eagle-import:R0805")
      (libsource (lib "eagle-import") (part "R-EU_R0805"))
    )
    (comp (ref "R60")
      (value "180R 0.1%")
      (footprint "eagle-import:R0805")
      (libsource (lib "eagle-import") (part "R-EU_R0805"))
    )
    (comp (ref "R61")
      (value "3K9 0.1%")
      (footprint "eagle-import:R0805")
      (libsource (lib "eagle-import") (part "R-EU_R0805"))
    )
    (comp (ref "R62")
      (value "2K2")
      (footprint "eagle-import:R0805")
      (libsource (lib "eagle-import") (part "R-EU_R0805"))
    )
    (comp (ref "R63")
      (value "51R 0.1%")
      (footprint "eagle-import:R0805")
      (libsource (lib "eagle-import") (part "R-EU_R0805"))
    )
    (comp (ref "R64")
      (value "51R 0.1%")
      (footprint "eagle-import:R0805")
      (libsource (lib "eagle-import") (part "R-EU_R0805"))
    )
    (comp (ref "R65")
      (value "2K2")
      (footprint "eagle-import:R0805")
      (libsource (lib "eagle-import") (part "R-EU_R0805"))
    )
    (comp (ref "R66")
      (value "R020/2W")
      (footprint "eagle-import:R2512")
      (libsource (lib "eagle-import") (part "R-EU_R2512"))
    )
    (comp (ref "R67")
      (value "51R 0.1%")
      (footprint "eagle-import:R0805")
      (libsource (lib "eagle-import") (part "R-EU_R0805"))
    )
    (comp (ref "R68")
      (value "51R 0.1%")
      (footprint "eagle-import:R0805")
      (libsource (lib "eagle-import") (part "R-EU_R0805"))
    )
    (comp (ref "R69")
      (value "3K9 0.1%")
      (footprint "eagle-import:R0805")
      (libsource (lib "eagle-import") (part "R-EU_R0805"))
    )
    (comp (ref "R70")
      (value "180R 0.1%")
      (footprint "eagle-import:R0805")
      (libsource (lib "eagle-import") (part "R-EU_R0805"))
    )
    (comp (ref "R71")
      (value "11K")
      (footprint "eagle-import:R0805")
      (libsource (lib "eagle-import") (part "R-EU_R0805"))
    )
    (comp (ref "R72")
      (value "10K")
      (footprint "eagle-import:R0805")
      (libsource (lib "eagle-import") (part "R-EU_R0805"))
    )
    (comp (ref "TP2")
      (value "TEST_POINT")
      (footprint "eagle-import:TP_1.1MM")
      (libsource (lib "eagle-import") (part "TEST_POINT"))
    )
    (comp (ref "ZD3")
      (value "See Note 3.2")
      (footprint "eagle-import:DO214AA")
      (libsource (lib "eagle-import") (part "P6SMB68A"))
    )
    (comp (ref "ZD4")
      (value "BZX384-C15.115")
      (footprint "eagle-import:SOD323-W")
      (libsource (lib "eagle-import") (part "ZENER-DIODESOD323"))
    )
    (comp (ref "ZD5")
      (value "PDZ6.2B")
      (footprint "eagle-import:SOD323-W")
      (libsource (lib "eagle-import") (part "ZENER-DIODESOD323"))
    )
    (comp (ref "C64")
      (value "100n")
      (footprint "eagle-import:C0603")
      (libsource (lib "eagle-import") (part "C-EUC0603"))
    )
    (comp (ref "C65")
      (value "10u")
      (footprint "eagle-import:C1206")
      (libsource (lib "eagle-import") (part "C-EUC1206"))
    )
    (comp (ref "C66")
      (value "10u")
      (footprint "eagle-import:EC1206")
      (libsource (lib "eagle-import") (part "ECAP1206"))
    )
    (comp (ref "C67")
      (value "1u")
      (footprint "eagle-import:C0805")
      (libsource (lib "eagle-import") (part "C-EUC0805"))
    )
    (comp (ref "C68")
      (value "100n")
      (footprint "eagle-import:C0603")
      (libsource (lib "eagle-import") (part "C-EUC0603"))
    )
    (comp (ref "C69")
      (value "100n")
      (footprint "eagle-import:C0603")
      (libsource (lib "eagle-import") (part "C-EUC0603"))
    )
    (comp (ref "C70")
      (value "3n3")
      (footprint "eagle-import:C0805")
      (libsource (lib "eagle-import") (part "C-EUC0805"))
    )
    (comp (ref "C71")
      (value "3n3")
      (footprint "eagle-import:C0805")
      (libsource (lib "eagle-import") (part "C-EUC0805"))
    )
    (comp (ref "C72")
      (value "100n")
      (footprint "eagle-import:C0603")
      (libsource (lib "eagle-import") (part "C-EUC0603"))
    )
    (comp (ref "C73")
      (value "1u")
      (footprint "eagle-import:C0805")
      (libsource (lib "eagle-import") (part "C-EUC0805"))
    )
    (comp (ref "C74")
      (value "100n")
      (footprint "eagle-import:C0603")
      (libsource (lib "eagle-import") (part "C-EUC0603"))
    )
    (comp (ref "C75")
      (value "1u")
      (footprint "eagle-import:C0805")
      (libsource (lib "eagle-import") (part "C-EUC0805"))
    )
    (comp (ref "C76")
      (value "3n3")
      (footprint "eagle-import:C0805")
      (libsource (lib "eagle-import") (part "C-EUC0805"))
    )
    (comp (ref "C77")
      (value "3n3")
      (footprint "eagle-import:C0805")
      (libsource (lib "eagle-import") (part "C-EUC0805"))
    )
    (comp (ref "C78")
      (value "100n")
      (footprint "eagle-import:C0603")
      (libsource (lib "eagle-import") (part "C-EUC0603"))
    )
    (comp (ref "IC9")
      (value "MCP23S08-E/SO")
      (footprint "eagle-import:SOIC127P1030X265-18N")
      (libsource (lib "eagle-import") (part "MCP23S08"))
    )
    (comp (ref "IC10")
      (value "REF5025")
      (footprint "eagle-import:SOIC127P600X175-8N")
      (libsource (lib "eagle-import") (part "REF50XX"))
    )
    (comp (ref "IC11")
      (value "DAC8552")
      (footprint "eagle-import:DGK8-M")
      (libsource (lib "eagle-import") (part "DAC8552_DGK_8M"))
    )
    (comp (ref "IC12")
      (value "ADG465SOT-23")
      (footprint "eagle-import:SOT95P280X145-6N")
      (libsource (lib "eagle-import") (part "ADG465SOT-23"))
    )
    (comp (ref "IC13")
      (value "TS5A9411DCKT")
      (footprint "eagle-import:SOT65P210X110-6N")
      (libsource (lib "eagle-import") (part "TS5A9411DCKT"))
    )
    (comp (ref "IC14")
      (value "ADS1120")
      (footprint "eagle-import:PW(R-PDSO-G16)")
      (libsource (lib "eagle-import") (part "ADS1120TSSOP-16"))
    )
    (comp (ref "JP2")
      (value "0R-JUMPA")
      (footprint "eagle-import:A0R-JMP")
      (libsource (lib "eagle-import") (part "0R-JUMPA"))
    )
    (comp (ref "Q14")
      (value "BSS84P")
      (footprint "eagle-import:SOT95P237X112-3N")
      (fields (field (name "MPN") "IRLML2246TRPBF"))
      (libsource (lib "eagle-import") (part "IRLML2246TRPBF"))
    )
    (comp (ref "Q15")
      (value "2N7002")
      (footprint "eagle-import:SOT103P240X110-3N")
      (fields
        (field (name "MPN") "2N7002-7-F")
        (field (name "MPN_1") "2N7002-7-F")
        (field (name "OC_FARNELL") "1713823")
        (field (name "OC_NEWARK") "25R5679")
        (field (name "PACKAGE") "SOT-23-3")
        (field (name "SUPPLIER") "DIODES INC.")
      )
      (libsource (lib "eagle-import") (part "2N7002"))
    )
    (comp (ref "R73")
      (value "100K")
      (footprint "eagle-import:R0805")
      (libsource (lib "eagle-import") (part "R-EU_R0805"))
    )
    (comp (ref "R74")
      (value "10K")
      (footprint "eagle-import:R0805")
      (libsource (lib "eagle-import") (part "R-EU_R0805"))
    )
    (comp (ref "R75")
      (value "100K")
      (footprint "eagle-import:R0805")
      (libsource (lib "eagle-import") (part "R-EU_R0805"))
    )
    (comp (ref "R76")
      (value "220R")
      (footprint "eagle-import:R0805")
      (libsource (lib "eagle-import") (part "R-EU_R0805"))
    )
    (comp (ref "R77")
      (value "220R")
      (footprint "eagle-import:R0805")
      (libsource (lib "eagle-import") (part "R-EU_R0805"))
    )
    (comp (ref "R78")
      (value "1K")
      (footprint "eagle-import:R0805")
      (libsource (lib "eagle-import") (part "R-EU_R0805"))
    )
    (comp (ref "R79")
      (value "220R")
      (footprint "eagle-import:R0805")
      (libsource (lib "eagle-import") (part "R-EU_R0805"))
    )
    (comp (ref "R80")
      (value "220R")
      (footprint "eagle-import:R0805")
      (libsource (lib "eagle-import") (part "R-EU_R0805"))
    )
    (comp (ref "R81")
      (value "10R")
      (footprint "eagle-import:R0805")
      (libsource (lib "eagle-import") (part "R-EU_R0805"))
    )
    (comp (ref "C79")
      (value "10n")
      (footprint "eagle-import:C0805")
      (libsource (lib "eagle-import") (part "C-EUC0805"))
    )
    (comp (ref "C80")
      (value "2n2")
      (footprint "eagle-import:C0805")
      (libsource (lib "eagle-import") (part "C-EUC0805"))
    )
    (comp (ref "C81")
      (value "100n")
      (footprint "eagle-import:C0603")
      (libsource (lib "eagle-import") (part "C-EUC0603"))
    )
    (comp (ref "C82")
      (value "100n")
      (footprint "eagle-import:C0603")
      (libsource (lib "eagle-import") (part "C-EUC0603"))
    )
    (comp (ref "C83")
      (value "10n")
      (footprint "eagle-import:C0805")
      (libsource (lib "eagle-import") (part "C-EUC0805"))
    )
    (comp (ref "IC15")
      (value "LP339D")
      (footprint "eagle-import:SOIC127P600X175-14N")
      (libsource (lib "eagle-import") (part "LM339SO14"))
    )
    (comp (ref "Q16")
      (value "MMBT5551")
      (footprint "eagle-import:SOT23-BEC")
      (libsource (lib "eagle-import") (part "-NPN-SOT23-BECMMBT5551LT1"))
    )
    (comp (ref "Q17")
      (value "MMBT5401")
      (footprint "eagle-import:SOT23-BEC")
      (libsource (lib "eagle-import") (part "-PNP-SOT23-BECBC857B"))
    )
    (comp (ref "Q18")
      (value "MMBT5551")
      (footprint "eagle-import:SOT23-BEC")
      (libsource (lib "eagle-import") (part "-NPN-SOT23-BECMMBT5551LT1"))
    )
    (comp (ref "Q19")
      (value "MMBT5551")
      (footprint "eagle-import:SOT23-BEC")
      (libsource (lib "eagle-import") (part "-NPN-SOT23-BECMMBT5551LT1"))
    )
    (comp (ref "R82")
      (value "10K")
      (footprint "eagle-import:R0805")
      (libsource (lib "eagle-import") (part "R-EU_R0805"))
    )
    (comp (ref "R83")
      (value "330R")
      (footprint "eagle-import:R0805")
      (libsource (lib "eagle-import") (part "R-EU_R0805"))
    )
    (comp (ref "R84")
      (value "47K")
      (footprint "eagle-import:R0805")
      (libsource (lib "eagle-import") (part "R-EU_R0805"))
    )
    (comp (ref "R85")
      (value "47K")
      (footprint "eagle-import:R0805")
      (libsource (lib "eagle-import") (part "R-EU_R0805"))
    )
    (comp (ref "R86")
      (value "5K1")
      (footprint "eagle-import:R0805")
      (libsource (lib "eagle-import") (part "R-EU_R0805"))
    )
    (comp (ref "R87")
      (value "47K")
      (footprint "eagle-import:R0805")
      (libsource (lib "eagle-import") (part "R-EU_R0805"))
    )
    (comp (ref "R88")
      (value "750R")
      (footprint "eagle-import:R0805")
      (libsource (lib "eagle-import") (part "R-EU_R0805"))
    )
    (comp (ref "R89")
      (value "5K6")
      (footprint "eagle-import:R0805")
      (libsource (lib "eagle-import") (part "R-EU_R0805"))
    )
    (comp (ref "R90")
      (value "3K3")
      (footprint "eagle-import:R0805")
      (libsource (lib "eagle-import") (part "R-EU_R0805"))
    )
    (comp (ref "R91")
      (value "2K2")
      (footprint "eagle-import:R0805")
      (libsource (lib "eagle-import") (part "R-EU_R0805"))
    )
    (comp (ref "R92")
      (value "10K")
      (footprint "eagle-import:R0805")
      (libsource (lib "eagle-import") (part "R-EU_R0805"))
    )
    (comp (ref "R93")
      (value "10K")
      (footprint "eagle-import:R0805")
      (libsource (lib "eagle-import") (part "R-EU_R0805"))
    )
    (comp (ref "R94")
      (value "750R")
      (footprint "eagle-import:R0805")
      (libsource (lib "eagle-import") (part "R-EU_R0805"))
    )
    (comp (ref "R95")
      (value "10K")
      (footprint "eagle-import:R0805")
      (libsource (lib "eagle-import") (part "R-EU_R0805"))
    )
    (comp (ref "R96")
      (value "47K")
      (footprint "eagle-import:R0805")
      (libsource (lib "eagle-import") (part "R-EU_R0805"))
    )
    (comp (ref "R97")
      (value "330R")
      (footprint "eagle-import:R0805")
      (libsource (lib "eagle-import") (part "R-EU_R0805"))
    )
    (comp (ref "R98")
      (value "5K1")
      (footprint "eagle-import:R0805")
      (libsource (lib "eagle-import") (part "R-EU_R0805"))
    )
    (comp (ref "R99")
      (value "12K")
      (footprint "eagle-import:R0805")
      (libsource (lib "eagle-import") (part "R-EU_R0805"))
    )
    (comp (ref "R100")
      (value "5K6")
      (footprint "eagle-import:R0805")
      (libsource (lib "eagle-import") (part "R-EU_R0805"))
    )
    (comp (ref "R101")
      (value "10K")
      (footprint "eagle-import:R0805")
      (libsource (lib "eagle-import") (part "R-EU_R0805"))
    )
  )
  (nets
    (net (code "1") (name "+5V") (class "Default")
      (node (ref "C64") (pin "1") (pinfunction "1_1") (pintype "passive"))
      (node (ref "C68") (pin "2") (pinfunction "2_2") (pintype "passive"))
      (node (ref "C72") (pin "2") (pinfunction "2_2") (pintype "passive"))
      (node (ref "C73") (pin "2") (pinfunction "2_2") (pintype "passive"))
      (node (ref "FB4") (pin "P$2") (pinfunction "2_P$2") (pintype "passive"))
      (node (ref "IC11") (pin "1") (pinfunction "VDD_1") (pintype "power_in"))
      (node (ref "IC14") (pin "13") (pinfunction "DVDD_13") (pintype "power_in"))
      (node (ref "IC9") (pin "18") (pinfunction "VDD_18") (pintype "power_in"))
      (node (ref "Q13") (pin "B") (pinfunction "B_B") (pintype "passive"))
      (node (ref "Q14") (pin "2") (pinfunction "S_2") (pintype "passive"))
      (node (ref "R73") (pin "1") (pinfunction "1_1") (pintype "passive"))
      (node (ref "R86") (pin "2") (pinfunction "2_2") (pintype "passive"))
      (node (ref "R92") (pin "2") (pinfunction "2_2") (pintype "passive"))
      (node (ref "R98") (pin "2") (pinfunction "2_2") (pintype "passive"))
      (node (ref "X3") (pin "2") (pinfunction "1_2") (pintype "passive"))
    )
    (net (code "2") (name "+VREF") (class "Default")
      (node (ref "C66") (pin "+") (pinfunction "+_+") (pintype "passive"))
      (node (ref "C69") (pin "2") (pinfunction "2_2") (pintype "passive"))
      (node (ref "C78") (pin "2") (pinfunction "2_2") (pintype "passive"))
      (node (ref "IC10") (pin "6") (pinfunction "VOUT_6") (pintype "output"))
      (node (ref "IC11") (pin "2") (pinfunction "VREF_2") (pintype "input"))
      (node (ref "IC14") (pin "9") (pinfunction "REFP0_9") (pintype "input"))
    )
    (net (code "3") (name "-9V") (class "Default")
      (node (ref "C25") (pin "2") (pinfunction "2_2") (pintype "passive"))
      (node (ref "C27") (pin "2") (pinfunction "-_2") (pintype "passive"))
      (node (ref "IC2") (pin "2") (pinfunction "IN_2") (pintype "input"))
      (node (ref "IC2") (pin "3") (pinfunction "IN_3") (pintype "input"))
      (node (ref "IC2") (pin "6") (pinfunction "IN_6") (pintype "input"))
      (node (ref "IC2") (pin "7") (pinfunction "IN_7") (pintype "input"))
      (node (ref "L5") (pin "2") (pinfunction "2_2") (pintype "passive"))
      (node (ref "R39") (pin "2") (pinfunction "2_2") (pintype "passive"))
      (node (ref "R40") (pin "2") (pinfunction "2_2") (pintype "passive"))
    )
    (net (code "4") (name "AC_IN1") (class "Default")
      (node (ref "D3") (pin "3") (pinfunction "C_3") (pintype "passive"))
      (node (ref "D4") (pin "1") (pinfunction "A1_1") (pintype "passive"))
      (node (ref "D4") (pin "2") (pinfunction "A2_2") (pintype "passive"))
      (node (ref "X2") (pin "1") (pinfunction "1_1") (pintype "bidirectional"))
      (node (ref "ZD2") (pin "A") (pinfunction "2_A") (pintype "passive"))
    )
    (net (code "5") (name "AC_IN2") (class "Default")
      (node (ref "D1") (pin "3") (pinfunction "C_3") (pintype "passive"))
      (node (ref "D2") (pin "1") (pinfunction "A1_1") (pintype "passive"))
      (node (ref "D2") (pin "2") (pinfunction "A2_2") (pintype "passive"))
      (node (ref "X2") (pin "2") (pinfunction "1_2") (pintype "bidirectional"))
      (node (ref "ZD2") (pin "C") (pinfunction "1_C") (pintype "passive"))
    )
    (net (code "6") (name "AUX_USET_IN") (class "Default")
      (node (ref "R78") (pin "2") (pinfunction "2_2") (pintype "passive"))
      (node (ref "X3") (pin "11") (pinfunction "1_11") (pintype "passive"))
    )
    (net (code "7") (name "AUX_USET_SW") (class "Default")
      (node (ref "IC13") (pin "1") (pinfunction "IN_1") (pintype "input"))
      (node (ref "IC9") (pin "14") (pinfunction "GP4_14") (pintype "bidirectional"))
    )
    (net (code "8") (name "CC_ACTIVE") (class "Default")
      (node (ref "IC9") (pin "12") (pinfunction "GP2_12") (pintype "bidirectional"))
      (node (ref "R100") (pin "2") (pinfunction "2_2") (pintype "passive"))
      (node (ref "R98") (pin "1") (pinfunction "1_1") (pintype "passive"))
    )
    (net (code "9") (name "CS_ADC") (class "Default")
      (node (ref "IC14") (pin "2") (pinfunction "~{CS}_2") (pintype "input"))
      (node (ref "X3") (pin "6") (pinfunction "1_6") (pintype "passive"))
    )
    (net (code "10") (name "CS_DAC") (class "Default")
      (node (ref "IC11") (pin "5") (pinfunction "~{SYNC}_5") (pintype "input"))
      (node (ref "X3") (pin "4") (pinfunction "1_4") (pintype "passive"))
    )
    (net (code "11") (name "CS_EXPANDER") (class "Default")
      (node (ref "IC9") (pin "7") (pinfunction "~{CS}_7") (pintype "input"))
      (node (ref "X3") (pin "3") (pinfunction "1_3") (pintype "passive"))
    )
    (net (code "12") (name "CV_ACTIVE") (class "Default")
      (node (ref "IC9") (pin "15") (pinfunction "GP5_15") (pintype "bidirectional"))
      (node (ref "R86") (pin "1") (pinfunction "1_1") (pintype "passive"))
      (node (ref "R89") (pin "2") (pinfunction "2_2") (pintype "passive"))
    )
    (net (code "13") (name "DC+") (class "Default")
      (node (ref "C2") (pin "2") (pinfunction "2_2") (pintype "passive"))
      (node (ref "L1") (pin "2") (pinfunction "1_2") (pintype "passive"))
      (node (ref "X1") (pin "2") (pinfunction "1_2") (pintype "bidirectional"))
      (node (ref "ZD1") (pin "C") (pinfunction "1_C") (pintype "passive"))
    )
    (net (code "14") (name "DC-") (class "Default")
      (node (ref "C2") (pin "1") (pinfunction "1_1") (pintype "passive"))
      (node (ref "L1") (pin "1") (pinfunction "1_1") (pintype "passive"))
      (node (ref "X1") (pin "3") (pinfunction "1_3") (pintype "bidirectional"))
      (node (ref "ZD1") (pin "A") (pinfunction "2_A") (pintype "passive"))
    )
    (net (code "15") (name "DC_OUT") (class "Default")
      (node (ref "C1") (pin "2") (pinfunction "2_2") (pintype "passive"))
      (node (ref "C10") (pin "1") (pinfunction "1_1") (pintype "passive"))
      (node (ref "C4") (pin "+") (pinfunction "+_+") (pintype "passive"))
      (node (ref "C43") (pin "1") (pinfunction "1_1") (pintype "passive"))
      (node (ref "C5") (pin "+") (pinfunction "+_+") (pintype "passive"))
      (node (ref "C6") (pin "1") (pinfunction "1_1") (pintype "passive"))
      (node (ref "C7") (pin "1") (pinfunction "1_1") (pintype "passive"))
      (node (ref "C8") (pin "1") (pinfunction "1_1") (pintype "passive"))
      (node (ref "C9") (pin "2") (pinfunction "2_2") (pintype "passive"))
      (node (ref "D2") (pin "3") (pinfunction "C_3") (pintype "passive"))
      (node (ref "D4") (pin "3") (pinfunction "C_3") (pintype "passive"))
      (node (ref "IC1") (pin "11") (pinfunction "VIN_11") (pintype "passive"))
      (node (ref "L1") (pin "3") (pinfunction "2_3") (pintype "passive"))
      (node (ref "L6") (pin "1") (pinfunction "1_1") (pintype "passive"))
      (node (ref "Q7") (pin "2") (pinfunction "C_2") (pintype "passive"))
      (node (ref "Q7") (pin "4") (pinfunction "C_4") (pintype "passive"))
      (node (ref "R1") (pin "1") (pinfunction "1_1") (pintype "passive"))
      (node (ref "R2") (pin "1") (pinfunction "1_1") (pintype "passive"))
      (node (ref "R36") (pin "2") (pinfunction "2_2") (pintype "passive"))
      (node (ref "R37") (pin "2") (pinfunction "2_2") (pintype "passive"))
    )
    (net (code "16") (name "EARTH") (class "Default")
      (node (ref "C1") (pin "1") (pinfunction "1_1") (pintype "passive"))
      (node (ref "C3") (pin "2") (pinfunction "2_2") (pintype "passive"))
      (node (ref "X1") (pin "1") (pinfunction "1_1") (pintype "bidirectional"))
    )
    (net (code "17") (name "GND") (class "Default")
      (node (ref "C10") (pin "2") (pinfunction "2_2") (pintype "passive"))
      (node (ref "C12") (pin "2") (pinfunction "2_2") (pintype "passive"))
      (node (ref "C18") (pin "2") (pinfunction "-_2") (pintype "passive"))
      (node (ref "C20") (pin "2") (pinfunction "2_2") (pintype "passive"))
      (node (ref "C24") (pin "2") (pinfunction "2_2") (pintype "passive"))
      (node (ref "C25") (pin "1") (pinfunction "1_1") (pintype "passive"))
      (node (ref "C26") (pin "1") (pinfunction "1_1") (pintype "passive"))
      (node (ref "C27") (pin "1") (pinfunction "+_1") (pintype "passive"))
      (node (ref "C29") (pin "2") (pinfunction "2_2") (pintype "passive"))
      (node (ref "C3") (pin "1") (pinfunction "1_1") (pintype "passive"))
      (node (ref "C30") (pin "2") (pinfunction "2_2") (pintype "passive"))
      (node (ref "C31") (pin "2") (pinfunction "2_2") (pintype "passive"))
      (node (ref "C33") (pin "2") (pinfunction "2_2") (pintype "passive"))
      (node (ref "C34") (pin "2") (pinfunction "-_2") (pintype "passive"))
      (node (ref "C35") (pin "2") (pinfunction "2_2") (pintype "passive"))
      (node (ref "C36") (pin "1") (pinfunction "1_1") (pintype "passive"))
      (node (ref "C37") (pin "2") (pinfunction "2_2") (pintype "passive"))
      (node (ref "C38") (pin "2") (pinfunction "2_2") (pintype "passive"))
      (node (ref "C39") (pin "1") (pinfunction "1_1") (pintype "passive"))
      (node (ref "C4") (pin "-") (pinfunction "-_-") (pintype "passive"))
      (node (ref "C41") (pin "2") (pinfunction "2_2") (pintype "passive"))
      (node (ref "C42") (pin "-") (pinfunction "-_-") (pintype "passive"))
      (node (ref "C43") (pin "2") (pinfunction "2_2") (pintype "passive"))
      (node (ref "C44") (pin "2") (pinfunction "2_2") (pintype "passive"))
      (node (ref "C5") (pin "-") (pinfunction "-_-") (pintype "passive"))
      (node (ref "C52") (pin "1") (pinfunction "1_1") (pintype "passive"))
      (node (ref "C53") (pin "2") (pinfunction "2_2") (pintype "passive"))
      (node (ref "C54") (pin "1") (pinfunction "1_1") (pintype "passive"))
      (node (ref "C55") (pin "1") (pinfunction "1_1") (pintype "passive"))
      (node (ref "C56") (pin "1") (pinfunction "1_1") (pintype "passive"))
      (node (ref "C57") (pin "1") (pinfunction "1_1") (pintype "passive"))
      (node (ref "C58") (pin "1") (pinfunction "1_1") (pintype "passive"))
      (node (ref "C59") (pin "2") (pinfunction "2_2") (pintype "passive"))
      (node (ref "C6") (pin "2") (pinfunction "2_2") (pintype "passive"))
      (node (ref "C60") (pin "1") (pinfunction "1_1") (pintype "passive"))
      (node (ref "C61") (pin "1") (pinfunction "1_1") (pintype "passive"))
      (node (ref "C64") (pin "2") (pinfunction "2_2") (pintype "passive"))
      (node (ref "C65") (pin "2") (pinfunction "2_2") (pintype "passive"))
      (node (ref "C66") (pin "-") (pinfunction "-_-") (pintype "passive"))
      (node (ref "C67") (pin "2") (pinfunction "2_2") (pintype "passive"))
      (node (ref "C68") (pin "1") (pinfunction "1_1") (pintype "passive"))
      (node (ref "C69") (pin "1") (pinfunction "1_1") (pintype "passive"))
      (node (ref "C7") (pin "2") (pinfunction "2_2") (pintype "passive"))
      (node (ref "C70") (pin "1") (pinfunction "1_1") (pintype "passive"))
      (node (ref "C71") (pin "2") (pinfunction "2_2") (pintype "passive"))
      (node (ref "C72") (pin "1") (pinfunction "1_1") (pintype "passive"))
      (node (ref "C73") (pin "1") (pinfunction "1_1") (pintype "passive"))
      (node (ref "C74") (pin "1") (pinfunction "1_1") (pintype "passive"))
      (node (ref "C75") (pin "1") (pinfunction "1_1") (pintype "passive"))
      (node (ref "C76") (pin "1") (pinfunction "1_1") (pintype "passive"))
      (node (ref "C77") (pin "1") (pinfunction "1_1") (pintype "passive"))
      (node (ref "C78") (pin "1") (pinfunction "1_1") (pintype "passive"))
      (node (ref "C8") (pin "2") (pinfunction "2_2") (pintype "passive"))
      (node (ref "C81") (pin "1") (pinfunction "1_1") (pintype "passive"))
      (node (ref "C82") (pin "1") (pinfunction "1_1") (pintype "passive"))
      (node (ref "D1") (pin "1") (pinfunction "A1_1") (pintype "passive"))
      (node (ref "D1") (pin "2") (pinfunction "A2_2") (pintype "passive"))
      (node (ref "D3") (pin "1") (pinfunction "A1_1") (pintype "passive"))
      (node (ref "D3") (pin "2") (pinfunction "A2_2") (pintype "passive"))
      (node (ref "D5") (pin "1") (pinfunction "A_1") (pintype "passive"))
      (node (ref "D5") (pin "2") (pinfunction "A_2") (pintype "passive"))
      (node (ref "D8") (pin "C") (pinfunction "C_C") (pintype "passive"))
      (node (ref "D9") (pin "A") (pinfunction "A_A") (pintype "passive"))
      (node (ref "GND") (pin "P$1") (pinfunction "P$1_P$1") (pintype "bidirectional"))
      (node (ref "IC1") (pin "TP") (pinfunction "PGND_TP") (pintype "passive"))
      (node (ref "IC10") (pin "4") (pinfunction "GND_4") (pintype "passive"))
      (node (ref "IC11") (pin "8") (pinfunction "GND_8") (pintype "power_in"))
      (node (ref "IC13") (pin "3") (pinfunction "GND_3") (pintype "passive"))
      (node (ref "IC14") (pin "3") (pinfunction "CLK_3") (pintype "bidirectional"))
      (node (ref "IC14") (pin "4") (pinfunction "DGND_4") (pintype "power_in"))
      (node (ref "IC14") (pin "5") (pinfunction "AVSS_5") (pintype "power_in"))
      (node (ref "IC14") (pin "8") (pinfunction "REFN0_8") (pintype "input"))
      (node (ref "IC2") (pin "5") (pinfunction "GND_5") (pintype "passive"))
      (node (ref "IC3") (pin "2") (pinfunction "GND_2") (pintype "passive"))
      (node (ref "IC3") (pin "3") (pinfunction "GND_3") (pintype "passive"))
      (node (ref "IC3") (pin "6") (pinfunction "GND_6") (pintype "passive"))
      (node (ref "IC3") (pin "7") (pinfunction "GND_7") (pintype "passive"))
      (node (ref "IC4") (pin "12") (pinfunction "PGND_12") (pintype "passive"))
      (node (ref "IC4") (pin "9") (pinfunction "AGND_9") (pintype "passive"))
      (node (ref "IC5") (pin "4") (pinfunction "GND_4") (pintype "passive"))
      (node (ref "IC7") (pin "5") (pinfunction "+IN_5") (pintype "input"))
      (node (ref "IC9") (pin "4") (pinfunction "A1_4") (pintype "input"))
      (node (ref "IC9") (pin "5") (pinfunction "A0_5") (pintype "input"))
      (node (ref "IC9") (pin "9") (pinfunction "VSS_9") (pintype "power_in"))
      (node (ref "L1") (pin "4") (pinfunction "2_4") (pintype "passive"))
      (node (ref "Q15") (pin "2") (pinfunction "S_2") (pintype "passive"))
      (node (ref "Q16") (pin "E") (pinfunction "E_E") (pintype "passive"))
      (node (ref "Q18") (pin "E") (pinfunction "E_E") (pintype "passive"))
      (node (ref "Q8") (pin "2") (pinfunction "D_2") (pintype "passive"))
      (node (ref "R1") (pin "2") (pinfunction "2_2") (pintype "passive"))
      (node (ref "R17") (pin "1") (pinfunction "1_1") (pintype "passive"))
      (node (ref "R20") (pin "2") (pinfunction "2_2") (pintype "passive"))
      (node (ref "R22") (pin "2") (pinfunction "2_2") (pintype "passive"))
      (node (ref "R25") (pin "2") (pinfunction "2_2") (pintype "passive"))
      (node (ref "R26") (pin "2") (pinfunction "2_2") (pintype "passive"))
      (node (ref "R42") (pin "1") (pinfunction "1_1") (pintype "passive"))
      (node (ref "R44") (pin "1") (pinfunction "1_1") (pintype "passive"))
      (node (ref "R48") (pin "1") (pinfunction "1_1") (pintype "passive"))
      (node (ref "R60") (pin "1") (pinfunction "1_1") (pintype "passive"))
      (node (ref "R75") (pin "1") (pinfunction "1_1") (pintype "passive"))
      (node (ref "R8") (pin "1") (pinfunction "1_1") (pintype "passive"))
      (node (ref "R84") (pin "1") (pinfunction "1_1") (pintype "passive"))
      (node (ref "R91") (pin "1") (pinfunction "1_1") (pintype "passive"))
      (node (ref "R95") (pin "2") (pinfunction "2_2") (pintype "passive"))
      (node (ref "R96") (pin "1") (pinfunction "1_1") (pintype "passive"))
      (node (ref "SH1") (pin "P$2") (pinfunction "GND_B_P$2") (pintype "bidirectional"))
      (node (ref "SH2") (pin "P$2") (pinfunction "GND_B_P$2") (pintype "bidirectional"))
      (node (ref "TP2") (pin "GND") (pinfunction "GND_GND") (pintype "bidirectional"))
      (node (ref "TR1") (pin "4") (pinfunction "4_4") (pintype "passive"))
      (node (ref "X3") (pin "10") (pinfunction "1_10") (pintype "passive"))
      (node (ref "X3") (pin "12") (pinfunction "1_12") (pintype "passive"))
      (node (ref "X3") (pin "14") (pinfunction "1_14") (pintype "passive"))
    )
    (net (code "18") (name "I_MON") (class "Default")
      (node (ref "IC8") (pin "6") (pinfunction "OUT_6") (pintype "output"))
      (node (ref "R65") (pin "1") (pinfunction "1_1") (pintype "passive"))
      (node (ref "R69") (pin "2") (pinfunction "2_2") (pintype "passive"))
      (node (ref "R80") (pin "1") (pinfunction "1_1") (pintype "passive"))
    )
    (net (code "19") (name "I_SERVO") (class "Default")
      (node (ref "C62") (pin "2") (pinfunction "2_2") (pintype "passive"))
      (node (ref "D17") (pin "C") (pinfunction "C_C") (pintype "passive"))
      (node (ref "D18") (pin "A") (pinfunction "A_A") (pintype "passive"))
      (node (ref "IC7") (pin "1") (pinfunction "OUT_1") (pintype "output"))
      (node (ref "R101") (pin "1") (pinfunction "1_1") (pintype "passive"))
    )
    (net (code "20") (name "I_SET") (class "Default")
      (node (ref "IC11") (pin "3") (pinfunction "VOUTB_3") (pintype "output"))
      (node (ref "R62") (pin "1") (pinfunction "1_1") (pintype "passive"))
      (node (ref "R76") (pin "1") (pinfunction "1_1") (pintype "passive"))
    )
    (net (code "21") (name "MCU_VCC") (class "Default")
      (node (ref "NTC1") (pin "2") (pinfunction "P$2_2") (pintype "bidirectional"))
      (node (ref "NTC1") (pin "2.1") (pinfunction "P$2_2.1") (pintype "bidirectional"))
      (node (ref "X3") (pin "15") (pinfunction "1_15") (pintype "passive"))
    )
    (net (code "22") (name "Net-(C13-Pad1)") (class "Default")
      (node (ref "C13") (pin "1") (pinfunction "1_1") (pintype "passive"))
      (node (ref "C19") (pin "2") (pinfunction "2_2") (pintype "passive"))
      (node (ref "L3") (pin "2") (pinfunction "2_2") (pintype "passive"))
      (node (ref "L4") (pin "1") (pinfunction "1_1") (pintype "passive"))
      (node (ref "R5") (pin "2") (pinfunction "2_2") (pintype "passive"))
      (node (ref "R6") (pin "1") (pinfunction "1_1") (pintype "passive"))
    )
    (net (code "23") (name "Net-(C14-Pad1)") (class "Default")
      (node (ref "C14") (pin "1") (pinfunction "1_1") (pintype "passive"))
      (node (ref "C15") (pin "1") (pinfunction "1_1") (pintype "passive"))
      (node (ref "C16") (pin "1") (pinfunction "1_1") (pintype "passive"))
      (node (ref "FB1") (pin "1") (pinfunction "1_1") (pintype "passive"))
      (node (ref "L4") (pin "2") (pinfunction "2_2") (pintype "passive"))
      (node (ref "R6") (pin "2") (pinfunction "2_2") (pintype "passive"))
    )
    (net (code "24") (name "Net-(C17-Pad2)") (class "Default")
      (node (ref "C17") (pin "2") (pinfunction "2_2") (pintype "passive"))
      (node (ref "R8") (pin "2") (pinfunction "2_2") (pintype "passive"))
    )
    (net (code "25") (name "Net-(C18-+)") (class "Default")
      (node (ref "C12") (pin "1") (pinfunction "1_1") (pintype "passive"))
      (node (ref "C18") (pin "1") (pinfunction "+_1") (pintype "passive"))
      (node (ref "C20") (pin "1") (pinfunction "1_1") (pintype "passive"))
      (node (ref "L2") (pin "2") (pinfunction "2_2") (pintype "passive"))
      (node (ref "L3") (pin "1") (pinfunction "1_1") (pintype "passive"))
      (node (ref "R10") (pin "1") (pinfunction "1_1") (pintype "passive"))
      (node (ref "R11") (pin "1") (pinfunction "1_1") (pintype "passive"))
      (node (ref "R12") (pin "1") (pinfunction "1_1") (pintype "passive"))
      (node (ref "R5") (pin "1") (pinfunction "1_1") (pintype "passive"))
    )
    (net (code "26") (name "Net-(C22-Pad1)") (class "Default")
      (node (ref "C22") (pin "1") (pinfunction "1_1") (pintype "passive"))
      (node (ref "R9") (pin "1") (pinfunction "1_1") (pintype "passive"))
    )
    (net (code "27") (name "Net-(C23-Pad2)") (class "Default")
      (node (ref "C23") (pin "2") (pinfunction "2_2") (pintype "passive"))
      (node (ref "D6") (pin "A") (pinfunction "A_A") (pintype "passive"))
      (node (ref "Q2") (pin "B") (pinfunction "B_B") (pintype "passive"))
      (node (ref "R11") (pin "2") (pinfunction "2_2") (pintype "passive"))
      (node (ref "R14") (pin "1") (pinfunction "1_1") (pintype "passive"))
    )
    (net (code "28") (name "Net-(C24-Pad1)") (class "Default")
      (node (ref "C24") (pin "1") (pinfunction "1_1") (pintype "passive"))
      (node (ref "D7") (pin "A") (pinfunction "A_A") (pintype "passive"))
      (node (ref "L5") (pin "1") (pinfunction "1_1") (pintype "passive"))
    )
    (net (code "29") (name "Net-(C32-Pad2)") (class "Default")
      (node (ref "C32") (pin "2") (pinfunction "2_2") (pintype "passive"))
      (node (ref "R18") (pin "2") (pinfunction "2_2") (pintype "passive"))
    )
    (net (code "30") (name "Net-(C34-+)") (class "Default")
      (node (ref "C34") (pin "1") (pinfunction "+_1") (pintype "passive"))
      (node (ref "C37") (pin "1") (pinfunction "1_1") (pintype "passive"))
      (node (ref "C38") (pin "1") (pinfunction "1_1") (pintype "passive"))
      (node (ref "IC4") (pin "11") (pinfunction "OUT_11") (pintype "output"))
      (node (ref "L7") (pin "1") (pinfunction "1_1") (pintype "passive"))
      (node (ref "R19") (pin "1") (pinfunction "1_1") (pintype "passive"))
      (node (ref "TR1") (pin "3") (pinfunction "3_3") (pintype "passive"))
    )
    (net (code "31") (name "Net-(C40-Pad2)") (class "Default")
      (node (ref "C40") (pin "2") (pinfunction "2_2") (pintype "passive"))
      (node (ref "R23") (pin "2") (pinfunction "2_2") (pintype "passive"))
    )
    (net (code "32") (name "Net-(C44-Pad1)") (class "Default")
      (node (ref "C44") (pin "1") (pinfunction "1_1") (pintype "passive"))
      (node (ref "R38") (pin "1") (pinfunction "1_1") (pintype "passive"))
    )
    (net (code "33") (name "Net-(C45-Pad2)") (class "Default")
      (node (ref "C45") (pin "2") (pinfunction "2_2") (pintype "passive"))
      (node (ref "R43") (pin "1") (pinfunction "1_1") (pintype "passive"))
    )
    (net (code "34") (name "Net-(C46-Pad2)") (class "Default")
      (node (ref "C46") (pin "2") (pinfunction "2_2") (pintype "passive"))
      (node (ref "R45") (pin "1") (pinfunction "1_1") (pintype "passive"))
    )
    (net (code "35") (name "Net-(C47-Pad1)") (class "Default")
      (node (ref "C47") (pin "1") (pinfunction "1_1") (pintype "passive"))
      (node (ref "R46") (pin "2") (pinfunction "2_2") (pintype "passive"))
      (node (ref "R47") (pin "1") (pinfunction "1_1") (pintype "passive"))
    )
    (net (code "36") (name "Net-(C48-Pad1)") (class "Default")
      (node (ref "C48") (pin "1") (pinfunction "1_1") (pintype "passive"))
      (node (ref "R56") (pin "2") (pinfunction "2_2") (pintype "passive"))
      (node (ref "R57") (pin "1") (pinfunction "1_1") (pintype "passive"))
    )
    (net (code "37") (name "Net-(C49-Pad2)") (class "Default")
      (node (ref "C49") (pin "2") (pinfunction "2_2") (pintype "passive"))
      (node (ref "R54") (pin "1") (pinfunction "1_1") (pintype "passive"))
    )
    (net (code "38") (name "Net-(C50-Pad2)") (class "Default")
      (node (ref "C50") (pin "2") (pinfunction "2_2") (pintype "passive"))
      (node (ref "R55") (pin "1") (pinfunction "1_1") (pintype "passive"))
    )
    (net (code "39") (name "Net-(C51-Pad2)") (class "Default")
      (node (ref "C51") (pin "2") (pinfunction "2_2") (pintype "passive"))
      (node (ref "R58") (pin "1") (pinfunction "1_1") (pintype "passive"))
    )
    (net (code "40") (name "Net-(C62-Pad1)") (class "Default")
      (node (ref "C62") (pin "1") (pinfunction "1_1") (pintype "passive"))
      (node (ref "R71") (pin "1") (pinfunction "1_1") (pintype "passive"))
    )
    (net (code "41") (name "Net-(C63-Pad2)") (class "Default")
      (node (ref "C63") (pin "2") (pinfunction "2_2") (pintype "passive"))
      (node (ref "R72") (pin "1") (pinfunction "1_1") (pintype "passive"))
    )
    (net (code "42") (name "Net-(C79-Pad2)") (class "Default")
      (node (ref "C79") (pin "2") (pinfunction "2_2") (pintype "passive"))
      (node (ref "Q17") (pin "B") (pinfunction "B_B") (pintype "passive"))
      (node (ref "R83") (pin "1") (pinfunction "1_1") (pintype "passive"))
      (node (ref "R88") (pin "2") (pinfunction "2_2") (pintype "passive"))
      (node (ref "R90") (pin "2") (pinfunction "2_2") (pintype "passive"))
    )
    (net (code "43") (name "Net-(C80-Pad1)") (class "Default")
      (node (ref "C80") (pin "1") (pinfunction "1_1") (pintype "passive"))
      (node (ref "Q16") (pin "B") (pinfunction "B_B") (pintype "passive"))
      (node (ref "R84") (pin "2") (pinfunction "2_2") (pintype "passive"))
      (node (ref "R85") (pin "2") (pinfunction "2_2") (pintype "passive"))
    )
    (net (code "44") (name "Net-(C80-Pad2)") (class "Default")
      (node (ref "C80") (pin "2") (pinfunction "2_2") (pintype "passive"))
      (node (ref "Q17") (pin "C") (pinfunction "C_C") (pintype "passive"))
      (node (ref "R85") (pin "1") (pinfunction "1_1") (pintype "passive"))
      (node (ref "R93") (pin "2") (pinfunction "2_2") (pintype "passive"))
    )
    (net (code "45") (name "Net-(C83-Pad1)") (class "Default")
      (node (ref "C83") (pin "1") (pinfunction "1_1") (pintype "passive"))
      (node (ref "Q19") (pin "B") (pinfunction "B_B") (pintype "passive"))
      (node (ref "R94") (pin "1") (pinfunction "1_1") (pintype "passive"))
      (node (ref "R97") (pin "2") (pinfunction "2_2") (pintype "passive"))
    )
    (net (code "46") (name "Net-(D5-C)") (class "Default")
      (node (ref "C17") (pin "1") (pinfunction "1_1") (pintype "passive"))
      (node (ref "D5") (pin "3") (pinfunction "C_3") (pintype "passive"))
      (node (ref "L2") (pin "1") (pinfunction "1_1") (pintype "passive"))
      (node (ref "Q1") (pin "2") (pinfunction "D_2") (pintype "passive"))
      (node (ref "R4") (pin "1") (pinfunction "1_1") (pintype "passive"))
    )
    (net (code "47") (name "Net-(D6-PadC)") (class "Default")
      (node (ref "D6") (pin "C") (pinfunction "C_C") (pintype "passive"))
      (node (ref "Q2") (pin "E") (pinfunction "E_E") (pintype "passive"))
      (node (ref "R10") (pin "2") (pinfunction "2_2") (pintype "passive"))
    )
    (net (code "48") (name "Net-(D7-PadC)") (class "Default")
      (node (ref "D7") (pin "C") (pinfunction "C_C") (pintype "passive"))
      (node (ref "TR1") (pin "2") (pinfunction "2_2") (pintype "passive"))
    )
    (net (code "49") (name "Net-(D11-PadC)") (class "Default")
      (node (ref "D11") (pin "C") (pinfunction "C_C") (pintype "passive"))
      (node (ref "D12") (pin "A") (pinfunction "A_A") (pintype "passive"))
      (node (ref "Q4") (pin "G") (pinfunction "G_G") (pintype "passive"))
      (node (ref "R30") (pin "1") (pinfunction "1_1") (pintype "passive"))
    )
    (net (code "50") (name "Net-(D12-PadC)") (class "Default")
      (node (ref "D12") (pin "C") (pinfunction "C_C") (pintype "passive"))
      (node (ref "ZD5") (pin "C") (pinfunction "C_C") (pintype "passive"))
    )
    (net (code "51") (name "Net-(D13-PadC)") (class "Default")
      (node (ref "D13") (pin "C") (pinfunction "C_C") (pintype "passive"))
      (node (ref "Q9") (pin "2") (pinfunction "C_2") (pintype "passive"))
      (node (ref "Q9") (pin "4") (pinfunction "C_4") (pintype "passive"))
      (node (ref "ZD5") (pin "A") (pinfunction "A_A") (pintype "passive"))
    )
    (net (code "52") (name "Net-(D14-PadC)") (class "Default")
      (node (ref "D14") (pin "C") (pinfunction "C_C") (pintype "passive"))
      (node (ref "Q6") (pin "C") (pinfunction "C_C") (pintype "passive"))
      (node (ref "ZD4") (pin "C") (pinfunction "C_C") (pintype "passive"))
    )
    (net (code "53") (name "Net-(D15-PadA)") (class "Default")
      (node (ref "D15") (pin "A") (pinfunction "A_A") (pintype "passive"))
      (node (ref "D17") (pin "A") (pinfunction "A_A") (pintype "passive"))
      (node (ref "R50") (pin "1") (pinfunction "1_1") (pintype "passive"))
    )
    (net (code "54") (name "Net-(FB2-1)") (class "Default")
      (node (ref "C26") (pin "2") (pinfunction "2_2") (pintype "passive"))
      (node (ref "D8") (pin "A") (pinfunction "A_A") (pintype "passive"))
      (node (ref "FB2") (pin "P$1") (pinfunction "1_P$1") (pintype "passive"))
      (node (ref "IC2") (pin "1") (pinfunction "OUT_1") (pintype "passive"))
    )
    (net (code "55") (name "Net-(FB3-1)") (class "Default")
      (node (ref "C29") (pin "1") (pinfunction "1_1") (pintype "passive"))
      (node (ref "D9") (pin "C") (pinfunction "C_C") (pintype "passive"))
      (node (ref "FB3") (pin "P$1") (pinfunction "1_P$1") (pintype "passive"))
      (node (ref "IC3") (pin "1") (pinfunction "VO_1") (pintype "passive"))
    )
    (net (code "56") (name "Net-(FB4-1)") (class "Default")
      (node (ref "C42") (pin "+") (pinfunction "+_+") (pintype "passive"))
      (node (ref "FB4") (pin "P$1") (pinfunction "1_P$1") (pintype "passive"))
      (node (ref "IC5") (pin "1") (pinfunction "OUT_1") (pintype "output"))
      (node (ref "R24") (pin "1") (pinfunction "1_1") (pintype "passive"))
      (node (ref "R27") (pin "1") (pinfunction "1_1") (pintype "passive"))
    )
    (net (code "57") (name "Net-(IC1-CAP)") (class "Default")
      (node (ref "C9") (pin "1") (pinfunction "1_1") (pintype "passive"))
      (node (ref "IC1") (pin "9") (pinfunction "CAP_9") (pintype "passive"))
    )
    (net (code "58") (name "Net-(IC1-FREQ)") (class "Default")
      (node (ref "IC1") (pin "2") (pinfunction "FREQ_2") (pintype "input"))
      (node (ref "R7") (pin "1") (pinfunction "1_1") (pintype "passive"))
    )
    (net (code "59") (name "Net-(IC1-GATE)") (class "Default")
      (node (ref "IC1") (pin "12") (pinfunction "GATE_12") (pintype "output"))
      (node (ref "Q1") (pin "1") (pinfunction "G_1") (pintype "passive"))
    )
    (net (code "60") (name "Net-(IC1-ITH)") (class "Default")
      (node (ref "C21") (pin "1") (pinfunction "1_1") (pintype "passive"))
      (node (ref "IC1") (pin "6") (pinfunction "ITH_6") (pintype "bidirectional"))
      (node (ref "R9") (pin "2") (pinfunction "2_2") (pintype "passive"))
    )
    (net (code "61") (name "Net-(IC1-PLLIN{slash}MODE)") (class "Default")
      (node (ref "IC1") (pin "1") (pinfunction "PLLIN/MODE_1") (pintype "input"))
      (node (ref "JP1") (pin "2") (pinfunction "2_2") (pintype "passive"))
    )
    (net (code "62") (name "Net-(IC1-RUN)") (class "Default")
      (node (ref "IC1") (pin "8") (pinfunction "RUN_8") (pintype "input"))
      (node (ref "R3") (pin "1") (pinfunction "1_1") (pintype "passive"))
    )
    (net (code "63") (name "Net-(IC1-SENSE)") (class "Default")
      (node (ref "IC1") (pin "10") (pinfunction "SENSE_10") (pintype "input"))
      (node (ref "Q1") (pin "3") (pinfunction "S_3") (pintype "passive"))
      (node (ref "R2") (pin "2") (pinfunction "2_2") (pintype "passive"))
    )
    (net (code "64") (name "Net-(IC1-SS)") (class "Default")
      (node (ref "C11") (pin "2") (pinfunction "2_2") (pintype "passive"))
      (node (ref "IC1") (pin "4") (pinfunction "SS_4") (pintype "input"))
    )
    (net (code "65") (name "Net-(IC1-VFB)") (class "Default")
      (node (ref "IC1") (pin "5") (pinfunction "VFB_5") (pintype "input"))
      (node (ref "Q3") (pin "2") (pinfunction "S_2") (pintype "passive"))
      (node (ref "R12") (pin "2") (pinfunction "2_2") (pintype "passive"))
      (node (ref "R13") (pin "2") (pinfunction "2_2") (pintype "passive"))
      (node (ref "R15") (pin "1") (pinfunction "1_1") (pintype "passive"))
    )
    (net (code "66") (name "Net-(IC3-VI)") (class "Default")
      (node (ref "C31") (pin "1") (pinfunction "1_1") (pintype "passive"))
      (node (ref "C35") (pin "1") (pinfunction "1_1") (pintype "passive"))
      (node (ref "C41") (pin "1") (pinfunction "1_1") (pintype "passive"))
      (node (ref "IC3") (pin "8") (pinfunction "VI_8") (pintype "input"))
      (node (ref "IC5") (pin "8") (pinfunction "IN_8") (pintype "power_in"))
      (node (ref "L7") (pin "2") (pinfunction "2_2") (pintype "passive"))
      (node (ref "LED1") (pin "A") (pinfunction "A_A") (pintype "passive"))
    )
    (net (code "67") (name "Net-(IC4-BST)") (class "Default")
      (node (ref "C28") (pin "2") (pinfunction "2_2") (pintype "passive"))
      (node (ref "IC4") (pin "16") (pinfunction "BST_16") (pintype "input"))
    )
    (net (code "68") (name "Net-(IC4-COMP)") (class "Default")
      (node (ref "IC4") (pin "5") (pinfunction "COMP_5") (pintype "input"))
      (node (ref "R23") (pin "1") (pinfunction "1_1") (pintype "passive"))
    )
    (net (code "69") (name "Net-(IC4-FB)") (class "Default")
      (node (ref "C40") (pin "1") (pinfunction "1_1") (pintype "passive"))
      (node (ref "IC4") (pin "6") (pinfunction "FB_6") (pintype "input"))
      (node (ref "R19") (pin "2") (pinfunction "2_2") (pintype "passive"))
      (node (ref "R25") (pin "1") (pinfunction "1_1") (pintype "passive"))
    )
    (net (code "70") (name "Net-(IC4-IS)") (class "Default")
      (node (ref "D10") (pin "A") (pinfunction "A_A") (pintype "passive"))
      (node (ref "IC4") (pin "13") (pinfunction "IS_13") (pintype "input"))
      (node (ref "R18") (pin "1") (pinfunction "1_1") (pintype "passive"))
    )
    (net (code "71") (name "Net-(IC4-PRE)") (class "Default")
      (node (ref "C28") (pin "1") (pinfunction "1_1") (pintype "passive"))
      (node (ref "C32") (pin "1") (pinfunction "1_1") (pintype "passive"))
      (node (ref "D10") (pin "C") (pinfunction "C_C") (pintype "passive"))
      (node (ref "IC4") (pin "14") (pinfunction "SW_14") (pintype "output"))
      (node (ref "IC4") (pin "15") (pinfunction "PRE_15") (pintype "input"))
      (node (ref "TR1") (pin "1") (pinfunction "1_1") (pintype "passive"))
    )
    (net (code "72") (name "Net-(IC4-RAMP)") (class "Default")
      (node (ref "C39") (pin "2") (pinfunction "2_2") (pintype "passive"))
      (node (ref "IC4") (pin "8") (pinfunction "RAMP_8") (pintype "input"))
    )
    (net (code "73") (name "Net-(IC4-RT)") (class "Default")
      (node (ref "IC4") (pin "7") (pinfunction "RT_7") (pintype "input"))
      (node (ref "R22") (pin "1") (pinfunction "1_1") (pintype "passive"))
    )
    (net (code "74") (name "Net-(IC4-SD)") (class "Default")
      (node (ref "IC4") (pin "2") (pinfunction "SD_2") (pintype "input"))
      (node (ref "R16") (pin "1") (pinfunction "1_1") (pintype "passive"))
      (node (ref "R17") (pin "2") (pinfunction "2_2") (pintype "passive"))
    )
    (net (code "75") (name "Net-(IC4-SS)") (class "Default")
      (node (ref "C33") (pin "1") (pinfunction "1_1") (pintype "passive"))
      (node (ref "IC4") (pin "10") (pinfunction "SS_10") (pintype "input"))
    )
    (net (code "76") (name "Net-(IC4-VCC)") (class "Default")
      (node (ref "C36") (pin "2") (pinfunction "2_2") (pintype "passive"))
      (node (ref "IC4") (pin "1") (pinfunction "VCC_1") (pintype "power_in"))
    )
    (net (code "77") (name "Net-(IC4-VIN)") (class "Default")
      (node (ref "C30") (pin "1") (pinfunction "1_1") (pintype "passive"))
      (node (ref "IC4") (pin "3") (pinfunction "VIN_3") (pintype "input"))
      (node (ref "L6") (pin "2") (pinfunction "2_2") (pintype "passive"))
      (node (ref "R16") (pin "2") (pinfunction "2_2") (pintype "passive"))
    )
    (net (code "78") (name "Net-(IC5-FB)") (class "Default")
      (node (ref "IC5") (pin "7") (pinfunction "FB_7") (pintype "input"))
      (node (ref "R24") (pin "2") (pinfunction "2_2") (pintype "passive"))
      (node (ref "R26") (pin "1") (pinfunction "1_1") (pintype "passive"))
    )
    (net (code "79") (name "Net-(IC6A-+IN)") (class "Default")
      (node (ref "IC6") (pin "3") (pinfunction "+IN_3") (pintype "input"))
      (node (ref "R45") (pin "2") (pinfunction "2_2") (pintype "passive"))
      (node (ref "R49") (pin "2") (pinfunction "2_2") (pintype "passive"))
    )
    (net (code "80") (name "Net-(IC6A--IN)") (class "Default")
      (node (ref "C49") (pin "1") (pinfunction "1_1") (pintype "passive"))
      (node (ref "D16") (pin "C") (pinfunction "C_C") (pintype "passive"))
      (node (ref "IC6") (pin "2") (pinfunction "-IN_2") (pintype "input"))
      (node (ref "R51") (pin "2") (pinfunction "2_2") (pintype "passive"))
      (node (ref "R55") (pin "2") (pinfunction "2_2") (pintype "passive"))
    )
    (net (code "81") (name "Net-(IC6B-+IN)") (class "Default")
      (node (ref "IC6") (pin "5") (pinfunction "+IN_5") (pintype "input"))
      (node (ref "R42") (pin "2") (pinfunction "2_2") (pintype "passive"))
      (node (ref "R43") (pin "2") (pinfunction "2_2") (pintype "passive"))
      (node (ref "R46") (pin "1") (pinfunction "1_1") (pintype "passive"))
    )
    (net (code "82") (name "Net-(IC6B--IN)") (class "Default")
      (node (ref "IC6") (pin "6") (pinfunction "-IN_6") (pintype "input"))
      (node (ref "R52") (pin "2") (pinfunction "2_2") (pintype "passive"))
      (node (ref "R56") (pin "1") (pinfunction "1_1") (pintype "passive"))
      (node (ref "R58") (pin "2") (pinfunction "2_2") (pintype "passive"))
    )
    (net (code "83") (name "Net-(IC7A-+IN)") (class "Default")
      (node (ref "IC7") (pin "3") (pinfunction "+IN_3") (pintype "input"))
      (node (ref "R62") (pin "2") (pinfunction "2_2") (pintype "passive"))
    )
    (net (code "84") (name "Net-(IC7A--IN)") (class "Default")
      (node (ref "D18") (pin "C") (pinfunction "C_C") (pintype "passive"))
      (node (ref "IC7") (pin "2") (pinfunction "-IN_2") (pintype "input"))
      (node (ref "R65") (pin "2") (pinfunction "2_2") (pintype "passive"))
      (node (ref "R71") (pin "2") (pinfunction "2_2") (pintype "passive"))
      (node (ref "R72") (pin "2") (pinfunction "2_2") (pintype "passive"))
    )
    (net (code "85") (name "Net-(IC7B--IN)") (class "Default")
      (node (ref "IC7") (pin "6") (pinfunction "-IN_6") (pintype "input"))
      (node (ref "IC7") (pin "7") (pinfunction "OUT_7") (pintype "output"))
    )
    (net (code "86") (name "Net-(IC8A-+IN)") (class "Default")
      (node (ref "IC8") (pin "3") (pinfunction "+IN_3") (pintype "input"))
      (node (ref "R61") (pin "2") (pinfunction "2_2") (pintype "passive"))
      (node (ref "R63") (pin "2") (pinfunction "2_2") (pintype "passive"))
    )
    (net (code "87") (name "Net-(IC8A--IN)") (class "Default")
      (node (ref "IC8") (pin "2") (pinfunction "-IN_2") (pintype "input"))
      (node (ref "R67") (pin "2") (pinfunction "2_2") (pintype "passive"))
      (node (ref "R70") (pin "1") (pinfunction "1_1") (pintype "passive"))
    )
    (net (code "88") (name "Net-(IC9-INT)") (class "Default")
      (node (ref "IC9") (pin "8") (pinfunction "INT_8") (pintype "output"))
      (node (ref "JP2") (pin "1") (pinfunction "1_1") (pintype "passive"))
    )
    (net (code "89") (name "Net-(IC10-TRIM{slash}NR)") (class "Default")
      (node (ref "C67") (pin "1") (pinfunction "1_1") (pintype "passive"))
      (node (ref "IC10") (pin "5") (pinfunction "TRIM/NR_5") (pintype "input"))
    )
    (net (code "90") (name "Net-(IC12-VD)") (class "Default")
      (node (ref "IC12") (pin "1") (pinfunction "VD_1") (pintype "bidirectional"))
      (node (ref "R78") (pin "1") (pinfunction "1_1") (pintype "passive"))
    )
    (net (code "91") (name "Net-(IC12-VS)") (class "Default")
      (node (ref "IC12") (pin "4") (pinfunction "VS_4") (pintype "bidirectional"))
      (node (ref "IC13") (pin "6") (pinfunction "S1_6") (pintype "bidirectional"))
    )
    (net (code "92") (name "Net-(IC13-D)") (class "Default")
      (node (ref "IC13") (pin "5") (pinfunction "D_5") (pintype "bidirectional"))
      (node (ref "R77") (pin "1") (pinfunction "1_1") (pintype "passive"))
    )
    (net (code "93") (name "Net-(IC14-AIN0{slash}REFP1)") (class "Default")
      (node (ref "C70") (pin "2") (pinfunction "2_2") (pintype "passive"))
      (node (ref "IC14") (pin "11") (pinfunction "AIN0/REFP1_11") (pintype "input"))
      (node (ref "R77") (pin "2") (pinfunction "2_2") (pintype "passive"))
    )
    (net (code "94") (name "Net-(IC14-AIN1)") (class "Default")
      (node (ref "C77") (pin "2") (pinfunction "2_2") (pintype "passive"))
      (node (ref "IC14") (pin "10") (pinfunction "AIN1_10") (pintype "input"))
      (node (ref "R79") (pin "2") (pinfunction "2_2") (pintype "passive"))
    )
    (net (code "95") (name "Net-(IC14-AIN2)") (class "Default")
      (node (ref "C76") (pin "2") (pinfunction "2_2") (pintype "passive"))
      (node (ref "IC14") (pin "7") (pinfunction "AIN2_7") (pintype "input"))
      (node (ref "R80") (pin "2") (pinfunction "2_2") (pintype "passive"))
    )
    (net (code "96") (name "Net-(IC14-AIN3{slash}REFN1)") (class "Default")
      (node (ref "C71") (pin "1") (pinfunction "1_1") (pintype "passive"))
      (node (ref "IC14") (pin "6") (pinfunction "AIN3/REFN1_6") (pintype "input"))
      (node (ref "R76") (pin "2") (pinfunction "2_2") (pintype "passive"))
    )
    (net (code "97") (name "Net-(IC14-AVDD)") (class "Default")
      (node (ref "C74") (pin "2") (pinfunction "2_2") (pintype "passive"))
      (node (ref "C75") (pin "2") (pinfunction "2_2") (pintype "passive"))
      (node (ref "IC14") (pin "12") (pinfunction "AVDD_12") (pintype "power_in"))
      (node (ref "R81") (pin "2") (pinfunction "2_2") (pintype "passive"))
    )
    (net (code "98") (name "Net-(IC15A-+IN)") (class "Default")
      (node (ref "IC15") (pin "7") (pinfunction "+IN_7") (pintype "input"))
      (node (ref "IC15") (pin "9") (pinfunction "+IN_9") (pintype "input"))
      (node (ref "R87") (pin "1") (pinfunction "1_1") (pintype "passive"))
      (node (ref "R91") (pin "2") (pinfunction "2_2") (pintype "passive"))
    )
    (net (code "99") (name "Net-(IC15A--IN)") (class "Default")
      (node (ref "IC15") (pin "5") (pinfunction "+IN_5") (pintype "input"))
      (node (ref "IC15") (pin "6") (pinfunction "-IN_6") (pintype "input"))
      (node (ref "R82") (pin "2") (pinfunction "2_2") (pintype "passive"))
    )
    (net (code "100") (name "Net-(IC15A-OUT)") (class "Default")
      (node (ref "IC15") (pin "1") (pinfunction "OUT_1") (pintype "open_collector"))
      (node (ref "IC15") (pin "2") (pinfunction "OUT_2") (pintype "open_collector"))
      (node (ref "R89") (pin "1") (pinfunction "1_1") (pintype "passive"))
    )
    (net (code "101") (name "Net-(IC15B--IN)") (class "Default")
      (node (ref "IC15") (pin "10") (pinfunction "-IN_10") (pintype "input"))
      (node (ref "IC15") (pin "4") (pinfunction "-IN_4") (pintype "input"))
      (node (ref "R95") (pin "1") (pinfunction "1_1") (pintype "passive"))
      (node (ref "R99") (pin "2") (pinfunction "2_2") (pintype "passive"))
    )
    (net (code "102") (name "Net-(IC15C--IN)") (class "Default")
      (node (ref "IC15") (pin "11") (pinfunction "+IN_11") (pintype "input"))
      (node (ref "IC15") (pin "8") (pinfunction "-IN_8") (pintype "input"))
      (node (ref "R101") (pin "2") (pinfunction "2_2") (pintype "passive"))
    )
    (net (code "103") (name "Net-(IC15C-OUT)") (class "Default")
      (node (ref "IC15") (pin "13") (pinfunction "OUT_13") (pintype "open_collector"))
      (node (ref "IC15") (pin "14") (pinfunction "OUT_14") (pintype "open_collector"))
      (node (ref "R100") (pin "1") (pinfunction "1_1") (pintype "passive"))
    )
    (net (code "104") (name "Net-(LED1-PadC)") (class "Default")
      (node (ref "LED1") (pin "C") (pinfunction "C_C") (pintype "passive"))
      (node (ref "R20") (pin "1") (pinfunction "1_1") (pintype "passive"))
    )
    (net (code "105") (name "Net-(Q3-D)") (class "Default")
      (node (ref "C23") (pin "1") (pinfunction "1_1") (pintype "passive"))
      (node (ref "Q2") (pin "C") (pinfunction "C_C") (pintype "passive"))
      (node (ref "Q3") (pin "3") (pinfunction "D_3") (pintype "passive"))
      (node (ref "R13") (pin "1") (pinfunction "1_1") (pintype "passive"))
    )
    (net (code "106") (name "Net-(Q4-PadS)") (class "Default")
      (node (ref "Q4") (pin "S") (pinfunction "S_S") (pintype "passive"))
      (node (ref "R28") (pin "1") (pinfunction "1_1") (pintype "passive"))
      (node (ref "R30") (pin "2") (pinfunction "2_2") (pintype "passive"))
      (node (ref "R31") (pin "2") (pinfunction "2_2") (pintype "passive"))
      (node (ref "R34") (pin "2") (pinfunction "2_2") (pintype "passive"))
      (node (ref "ZD4") (pin "A") (pinfunction "A_A") (pintype "passive"))
    )
    (net (code "107") (name "Net-(Q5-PadB)") (class "Default")
      (node (ref "Q5") (pin "B") (pinfunction "B_B") (pintype "passive"))
      (node (ref "R32") (pin "2") (pinfunction "2_2") (pintype "passive"))
    )
    (net (code "108") (name "Net-(Q6-PadB)") (class "Default")
      (node (ref "Q6") (pin "B") (pinfunction "B_B") (pintype "passive"))
      (node (ref "R31") (pin "1") (pinfunction "1_1") (pintype "passive"))
    )
    (net (code "109") (name "Net-(Q7-B)") (class "Default")
      (node (ref "D14") (pin "A") (pinfunction "A_A") (pintype "passive"))
      (node (ref "Q7") (pin "1") (pinfunction "B_1") (pintype "passive"))
      (node (ref "R38") (pin "2") (pinfunction "2_2") (pintype "passive"))
      (node (ref "R41") (pin "1") (pinfunction "1_1") (pintype "passive"))
    )
    (net (code "110") (name "Net-(Q7-E)") (class "Default")
      (node (ref "D11") (pin "A") (pinfunction "A_A") (pintype "passive"))
      (node (ref "Q7") (pin "3") (pinfunction "E_3") (pintype "passive"))
    )
    (net (code "111") (name "Net-(Q8-G)") (class "Default")
      (node (ref "D13") (pin "A") (pinfunction "A_A") (pintype "passive"))
      (node (ref "Q5") (pin "C") (pinfunction "C_C") (pintype "passive"))
      (node (ref "Q8") (pin "1") (pinfunction "G_1") (pintype "passive"))
      (node (ref "R33") (pin "2") (pinfunction "2_2") (pintype "passive"))
    )
    (net (code "112") (name "Net-(Q8-S)") (class "Default")
      (node (ref "Q8") (pin "3") (pinfunction "S_3") (pintype "passive"))
      (node (ref "R29") (pin "1") (pinfunction "1_1") (pintype "passive"))
      (node (ref "R32") (pin "1") (pinfunction "1_1") (pintype "passive"))
      (node (ref "R33") (pin "1") (pinfunction "1_1") (pintype "passive"))
    )
    (net (code "113") (name "Net-(Q9-E)") (class "Default")
      (node (ref "Q9") (pin "3") (pinfunction "E_3") (pintype "passive"))
      (node (ref "R40") (pin "1") (pinfunction "1_1") (pintype "passive"))
    )
    (net (code "114") (name "Net-(Q10-PadB)") (class "Default")
      (node (ref "Q10") (pin "B") (pinfunction "B_B") (pintype "passive"))
      (node (ref "Q10") (pin "C") (pinfunction "C_C") (pintype "passive"))
      (node (ref "Q11") (pin "B") (pinfunction "B_B") (pintype "passive"))
      (node (ref "Q13") (pin "C") (pinfunction "C_C") (pintype "passive"))
    )
    (net (code "115") (name "Net-(Q10-PadE)") (class "Default")
      (node (ref "Q10") (pin "E") (pinfunction "E_E") (pintype "passive"))
      (node (ref "R36") (pin "1") (pinfunction "1_1") (pintype "passive"))
    )
    (net (code "116") (name "Net-(Q11-PadE)") (class "Default")
      (node (ref "Q11") (pin "E") (pinfunction "E_E") (pintype "passive"))
      (node (ref "R37") (pin "1") (pinfunction "1_1") (pintype "passive"))
    )
    (net (code "117") (name "Net-(Q12-PadB)") (class "Default")
      (node (ref "Q12") (pin "B") (pinfunction "B_B") (pintype "passive"))
      (node (ref "R34") (pin "1") (pinfunction "1_1") (pintype "passive"))
      (node (ref "R44") (pin "2") (pinfunction "2_2") (pintype "passive"))
    )
    (net (code "118") (name "Net-(Q12-PadE)") (class "Default")
      (node (ref "Q12") (pin "E") (pinfunction "E_E") (pintype "passive"))
      (node (ref "R50") (pin "2") (pinfunction "2_2") (pintype "passive"))
    )
    (net (code "119") (name "Net-(Q13-PadE)") (class "Default")
      (node (ref "Q13") (pin "E") (pinfunction "E_E") (pintype "passive"))
      (node (ref "R53") (pin "2") (pinfunction "2_2") (pintype "passive"))
    )
    (net (code "120") (name "Net-(Q14-D)") (class "Default")
      (node (ref "Q14") (pin "3") (pinfunction "D_3") (pintype "passive"))
      (node (ref "R74") (pin "2") (pinfunction "2_2") (pintype "passive"))
    )
    (net (code "121") (name "Net-(Q18-PadB)") (class "Default")
      (node (ref "Q18") (pin "B") (pinfunction "B_B") (pintype "passive"))
      (node (ref "R93") (pin "1") (pinfunction "1_1") (pintype "passive"))
      (node (ref "R96") (pin "2") (pinfunction "2_2") (pintype "passive"))
    )
    (net (code "122") (name "Net-(Q19-PadC)") (class "Default")
      (node (ref "Q19") (pin "C") (pinfunction "C_C") (pintype "passive"))
      (node (ref "R90") (pin "1") (pinfunction "1_1") (pintype "passive"))
    )
    (net (code "123") (name "Net-(R4-Pad2)") (class "Default")
      (node (ref "R4") (pin "2") (pinfunction "2_2") (pintype "passive"))
      (node (ref "SW") (pin "P$1") (pinfunction "P$1_P$1") (pintype "bidirectional"))
    )
    (net (code "124") (name "Net-(R60-Pad2)") (class "Default")
      (node (ref "R60") (pin "2") (pinfunction "2_2") (pintype "passive"))
      (node (ref "R61") (pin "1") (pinfunction "1_1") (pintype "passive"))
    )
    (net (code "125") (name "Net-(R63-Pad1)") (class "Default")
      (node (ref "R63") (pin "1") (pinfunction "1_1") (pintype "passive"))
      (node (ref "R64") (pin "2") (pinfunction "2_2") (pintype "passive"))
    )
    (net (code "126") (name "Net-(R67-Pad1)") (class "Default")
      (node (ref "R67") (pin "1") (pinfunction "1_1") (pintype "passive"))
      (node (ref "R68") (pin "2") (pinfunction "2_2") (pintype "passive"))
    )
    (net (code "127") (name "Net-(R69-Pad1)") (class "Default")
      (node (ref "R69") (pin "1") (pinfunction "1_1") (pintype "passive"))
      (node (ref "R70") (pin "2") (pinfunction "2_2") (pintype "passive"))
    )
    (net (code "128") (name "Net-(X3H-1)") (class "Default")
      (node (ref "R21") (pin "2") (pinfunction "2_2") (pintype "passive"))
      (node (ref "X3") (pin "16") (pinfunction "1_16") (pintype "passive"))
    )
    (net (code "129") (name "OUT+") (class "Default")
      (node (ref "C47") (pin "2") (pinfunction "2_2") (pintype "passive"))
      (node (ref "C50") (pin "1") (pinfunction "1_1") (pintype "passive"))
      (node (ref "C63") (pin "1") (pinfunction "1_1") (pintype "passive"))
      (node (ref "C79") (pin "1") (pinfunction "1_1") (pintype "passive"))
      (node (ref "Q17") (pin "E") (pinfunction "E_E") (pintype "passive"))
      (node (ref "Q5") (pin "E") (pinfunction "E_E") (pintype "passive"))
      (node (ref "Q6") (pin "E") (pinfunction "E_E") (pintype "passive"))
      (node (ref "R14") (pin "2") (pinfunction "2_2") (pintype "passive"))
      (node (ref "R28") (pin "2") (pinfunction "2_2") (pintype "passive"))
      (node (ref "R29") (pin "2") (pinfunction "2_2") (pintype "passive"))
      (node (ref "R35") (pin "1") (pinfunction "1_1") (pintype "passive"))
      (node (ref "R83") (pin "2") (pinfunction "2_2") (pintype "passive"))
      (node (ref "TP2") (pin "TIP") (pinfunction "TIP_TIP") (pintype "bidirectional"))
      (node (ref "X3") (pin "23") (pinfunction "1_23") (pintype "passive"))
      (node (ref "X3") (pin "24") (pinfunction "1_24") (pintype "passive"))
      (node (ref "X3") (pin "25") (pinfunction "1_25") (pintype "passive"))
      (node (ref "X3") (pin "26") (pinfunction "1_26") (pintype "passive"))
      (node (ref "ZD3") (pin "C") (pinfunction "1_C") (pintype "passive"))
    )
    (net (code "130") (name "OUT-") (class "Default")
      (node (ref "C46") (pin "1") (pinfunction "1_1") (pintype "passive"))
      (node (ref "C48") (pin "2") (pinfunction "2_2") (pintype "passive"))
      (node (ref "C83") (pin "2") (pinfunction "2_2") (pintype "passive"))
      (node (ref "Q19") (pin "E") (pinfunction "E_E") (pintype "passive"))
      (node (ref "R59") (pin "2") (pinfunction "2_2") (pintype "passive"))
      (node (ref "R64") (pin "1") (pinfunction "1_1") (pintype "passive"))
      (node (ref "R66") (pin "1") (pinfunction "1_1") (pintype "passive"))
      (node (ref "R97") (pin "1") (pinfunction "1_1") (pintype "passive"))
      (node (ref "X3") (pin "17") (pinfunction "1_17") (pintype "passive"))
      (node (ref "X3") (pin "18") (pinfunction "1_18") (pintype "passive"))
      (node (ref "X3") (pin "19") (pinfunction "1_19") (pintype "passive"))
      (node (ref "X3") (pin "20") (pinfunction "1_20") (pintype "passive"))
      (node (ref "ZD3") (pin "A") (pinfunction "2_A") (pintype "passive"))
    )
    (net (code "131") (name "POST_OE") (class "Default")
      (node (ref "Q15") (pin "3") (pinfunction "D_3") (pintype "passive"))
      (node (ref "R53") (pin "1") (pinfunction "1_1") (pintype "passive"))
    )
    (net (code "132") (name "POUT-") (class "Default")
      (node (ref "C13") (pin "2") (pinfunction "2_2") (pintype "passive"))
      (node (ref "C14") (pin "2") (pinfunction "2_2") (pintype "passive"))
      (node (ref "C15") (pin "2") (pinfunction "2_2") (pintype "passive"))
      (node (ref "C16") (pin "2") (pinfunction "2_2") (pintype "passive"))
      (node (ref "C19") (pin "1") (pinfunction "1_1") (pintype "passive"))
      (node (ref "R66") (pin "2") (pinfunction "2_2") (pintype "passive"))
      (node (ref "R68") (pin "1") (pinfunction "1_1") (pintype "passive"))
      (node (ref "SH1") (pin "P$1") (pinfunction "GND_A_P$1") (pintype "bidirectional"))
      (node (ref "TP1") (pin "GND") (pinfunction "GND_GND") (pintype "bidirectional"))
    )
    (net (code "133") (name "PREG_OUT") (class "Default")
      (node (ref "FB1") (pin "2") (pinfunction "2_2") (pintype "passive"))
      (node (ref "Q4") (pin "D") (pinfunction "D_D") (pintype "passive"))
      (node (ref "TP1") (pin "TIP") (pinfunction "TIP_TIP") (pintype "bidirectional"))
    )
    (net (code "134") (name "PRE_OE") (class "Default")
      (node (ref "IC9") (pin "17") (pinfunction "GP7_17") (pintype "bidirectional"))
      (node (ref "Q15") (pin "1") (pinfunction "G_1") (pintype "passive"))
      (node (ref "R3") (pin "2") (pinfunction "2_2") (pintype "passive"))
      (node (ref "R75") (pin "2") (pinfunction "2_2") (pintype "passive"))
    )
    (net (code "135") (name "PS_MISO") (class "Default")
      (node (ref "IC14") (pin "15") (pinfunction "DOUT/~{DRDY}_15") (pintype "output"))
      (node (ref "IC9") (pin "3") (pinfunction "SO_3") (pintype "output"))
      (node (ref "X3") (pin "9") (pinfunction "1_9") (pintype "passive"))
    )
    (net (code "136") (name "PS_MOSI") (class "Default")
      (node (ref "IC11") (pin "7") (pinfunction "DIN_7") (pintype "input"))
      (node (ref "IC14") (pin "16") (pinfunction "DIN_16") (pintype "input"))
      (node (ref "IC9") (pin "2") (pinfunction "SI_2") (pintype "input"))
      (node (ref "X3") (pin "1") (pinfunction "1_1") (pintype "passive"))
    )
    (net (code "137") (name "PS_SCLK") (class "Default")
      (node (ref "IC11") (pin "6") (pinfunction "SCLK_6") (pintype "input"))
      (node (ref "IC14") (pin "1") (pinfunction "SCLK_1") (pintype "input"))
      (node (ref "IC9") (pin "1") (pinfunction "SCK_1") (pintype "input"))
      (node (ref "X3") (pin "7") (pinfunction "1_7") (pintype "passive"))
    )
    (net (code "138") (name "PWRGOOD") (class "Default")
      (node (ref "IC5") (pin "5") (pinfunction "~{ERROR}_5") (pintype "input"))
      (node (ref "IC9") (pin "16") (pinfunction "GP6_16") (pintype "bidirectional"))
      (node (ref "R27") (pin "2") (pinfunction "2_2") (pintype "passive"))
    )
    (net (code "139") (name "SENSE+") (class "Default")
      (node (ref "C45") (pin "1") (pinfunction "1_1") (pintype "passive"))
      (node (ref "R35") (pin "2") (pinfunction "2_2") (pintype "passive"))
      (node (ref "R47") (pin "2") (pinfunction "2_2") (pintype "passive"))
      (node (ref "R88") (pin "1") (pinfunction "1_1") (pintype "passive"))
      (node (ref "X3") (pin "22") (pinfunction "1_22") (pintype "passive"))
    )
    (net (code "140") (name "SENSE-") (class "Default")
      (node (ref "C51") (pin "1") (pinfunction "1_1") (pintype "passive"))
      (node (ref "R57") (pin "2") (pinfunction "2_2") (pintype "passive"))
      (node (ref "R59") (pin "1") (pinfunction "1_1") (pintype "passive"))
      (node (ref "R94") (pin "2") (pinfunction "2_2") (pintype "passive"))
      (node (ref "X3") (pin "21") (pinfunction "1_21") (pintype "passive"))
    )
    (net (code "141") (name "SENSE_ERR") (class "Default")
      (node (ref "IC9") (pin "10") (pinfunction "GP0_10") (pintype "bidirectional"))
      (node (ref "Q18") (pin "C") (pinfunction "C_C") (pintype "passive"))
      (node (ref "R92") (pin "1") (pinfunction "1_1") (pintype "passive"))
    )
    (net (code "142") (name "SENSE_PROT") (class "Default")
      (node (ref "Q11") (pin "C") (pinfunction "C_C") (pintype "passive"))
      (node (ref "Q12") (pin "C") (pinfunction "C_C") (pintype "passive"))
      (node (ref "Q16") (pin "C") (pinfunction "C_C") (pintype "passive"))
      (node (ref "R41") (pin "2") (pinfunction "2_2") (pintype "passive"))
      (node (ref "R48") (pin "2") (pinfunction "2_2") (pintype "passive"))
    )
    (net (code "143") (name "SGND") (class "Default")
      (node (ref "C11") (pin "1") (pinfunction "1_1") (pintype "passive"))
      (node (ref "C21") (pin "2") (pinfunction "2_2") (pintype "passive"))
      (node (ref "C22") (pin "2") (pinfunction "2_2") (pintype "passive"))
      (node (ref "IC1") (pin "3") (pinfunction "SGND_3") (pintype "passive"))
      (node (ref "JP1") (pin "1") (pinfunction "1_1") (pintype "passive"))
      (node (ref "R15") (pin "2") (pinfunction "2_2") (pintype "passive"))
      (node (ref "R7") (pin "2") (pinfunction "2_2") (pintype "passive"))
      (node (ref "SH2") (pin "P$1") (pinfunction "GND_A_P$1") (pintype "bidirectional"))
    )
    (net (code "144") (name "SYNC") (class "Default")
      (node (ref "IC4") (pin "4") (pinfunction "SYNC_4") (pintype "input"))
      (node (ref "JP1") (pin "3") (pinfunction "3_3") (pintype "passive"))
      (node (ref "R21") (pin "1") (pinfunction "1_1") (pintype "passive"))
    )
    (net (code "145") (name "TEMP_NTC") (class "Default")
      (node (ref "NTC1") (pin "1") (pinfunction "P$1_1") (pintype "bidirectional"))
      (node (ref "NTC1") (pin "1.1") (pinfunction "P$1_1.1") (pintype "bidirectional"))
      (node (ref "X3") (pin "13") (pinfunction "1_13") (pintype "passive"))
    )
    (net (code "146") (name "U_MON") (class "Default")
      (node (ref "IC6") (pin "7") (pinfunction "OUT_7") (pintype "output"))
      (node (ref "R51") (pin "1") (pinfunction "1_1") (pintype "passive"))
      (node (ref "R52") (pin "1") (pinfunction "1_1") (pintype "passive"))
      (node (ref "R79") (pin "1") (pinfunction "1_1") (pintype "passive"))
    )
    (net (code "147") (name "U_SERVO") (class "Default")
      (node (ref "D15") (pin "C") (pinfunction "C_C") (pintype "passive"))
      (node (ref "D16") (pin "A") (pinfunction "A_A") (pintype "passive"))
      (node (ref "IC6") (pin "1") (pinfunction "OUT_1") (pintype "output"))
      (node (ref "R54") (pin "2") (pinfunction "2_2") (pintype "passive"))
      (node (ref "R82") (pin "1") (pinfunction "1_1") (pintype "passive"))
    )
    (net (code "148") (name "U_SET_OUT") (class "Default")
      (node (ref "IC11") (pin "4") (pinfunction "VOUTA_4") (pintype "output"))
      (node (ref "IC13") (pin "4") (pinfunction "S2_4") (pintype "bidirectional"))
      (node (ref "R49") (pin "1") (pinfunction "1_1") (pintype "passive"))
    )
    (net (code "149") (name "V+") (class "Default")
      (node (ref "C52") (pin "2") (pinfunction "2_2") (pintype "passive"))
      (node (ref "C53") (pin "1") (pinfunction "1_1") (pintype "passive"))
      (node (ref "C54") (pin "2") (pinfunction "2_2") (pintype "passive"))
      (node (ref "C55") (pin "2") (pinfunction "2_2") (pintype "passive"))
      (node (ref "C56") (pin "2") (pinfunction "2_2") (pintype "passive"))
      (node (ref "C65") (pin "1") (pinfunction "1_1") (pintype "passive"))
      (node (ref "C81") (pin "2") (pinfunction "2_2") (pintype "passive"))
      (node (ref "FB3") (pin "P$2") (pinfunction "2_P$2") (pintype "passive"))
      (node (ref "IC10") (pin "2") (pinfunction "VIN_2") (pintype "passive"))
      (node (ref "IC12") (pin "6") (pinfunction "VDD_6") (pintype "bidirectional"))
      (node (ref "IC13") (pin "2") (pinfunction "VDD_2") (pintype "power_in"))
      (node (ref "IC15") (pin "3") (pinfunction "V+_3") (pintype "power_in"))
      (node (ref "IC6") (pin "8") (pinfunction "V+_8") (pintype "power_in"))
      (node (ref "IC7") (pin "8") (pinfunction "V+_8") (pintype "power_in"))
      (node (ref "IC8") (pin "7") (pinfunction "V+_7") (pintype "power_in"))
      (node (ref "R81") (pin "1") (pinfunction "1_1") (pintype "passive"))
      (node (ref "R87") (pin "2") (pinfunction "2_2") (pintype "passive"))
    )
    (net (code "150") (name "V-") (class "Default")
      (node (ref "C57") (pin "2") (pinfunction "2_2") (pintype "passive"))
      (node (ref "C58") (pin "2") (pinfunction "2_2") (pintype "passive"))
      (node (ref "C59") (pin "1") (pinfunction "1_1") (pintype "passive"))
      (node (ref "C60") (pin "2") (pinfunction "2_2") (pintype "passive"))
      (node (ref "C61") (pin "2") (pinfunction "2_2") (pintype "passive"))
      (node (ref "C82") (pin "2") (pinfunction "2_2") (pintype "passive"))
      (node (ref "FB2") (pin "P$2") (pinfunction "2_P$2") (pintype "passive"))
      (node (ref "IC12") (pin "3") (pinfunction "VSS_3") (pintype "bidirectional"))
      (node (ref "IC15") (pin "12") (pinfunction "GND_12") (pintype "power_in"))
      (node (ref "IC6") (pin "4") (pinfunction "V-_4") (pintype "power_in"))
      (node (ref "IC7") (pin "4") (pinfunction "V-_4") (pintype "power_in"))
      (node (ref "IC8") (pin "4") (pinfunction "V-_4") (pintype "power_in"))
      (node (ref "R99") (pin "1") (pinfunction "1_1") (pintype "passive"))
    )
    (net (code "151") (name "unconnected-(IC1-PGOOD-Pad7)") (class "Default")
      (node (ref "IC1") (pin "7") (pinfunction "PGOOD_7") (pintype "output"))
    )
    (net (code "152") (name "unconnected-(IC5-SD-Pad3)") (class "Default")
      (node (ref "IC5") (pin "3") (pinfunction "SD_3") (pintype "input"))
    )
    (net (code "153") (name "unconnected-(IC5-SENSE-Pad2)") (class "Default")
      (node (ref "IC5") (pin "2") (pinfunction "SENSE_2") (pintype "input"))
    )
    (net (code "154") (name "unconnected-(IC5-VTAP-Pad6)") (class "Default")
      (node (ref "IC5") (pin "6") (pinfunction "VTAP_6") (pintype "input"))
    )
    (net (code "155") (name "unconnected-(IC10-TEMP-Pad3)") (class "Default")
      (node (ref "IC10") (pin "3") (pinfunction "TEMP_3") (pintype "input"))
    )
    (net (code "156") (name "~{DP_DRIVE}") (class "Default")
      (node (ref "Q9") (pin "1") (pinfunction "B_1") (pintype "passive"))
      (node (ref "R39") (pin "1") (pinfunction "1_1") (pintype "passive"))
      (node (ref "R74") (pin "1") (pinfunction "1_1") (pintype "passive"))
    )
    (net (code "157") (name "~{INT}") (class "Default")
      (node (ref "JP2") (pin "2") (pinfunction "2_2") (pintype "passive"))
      (node (ref "X3") (pin "8") (pinfunction "1_8") (pintype "passive"))
    )
    (net (code "158") (name "~{PS_DRDY}") (class "Default")
      (node (ref "IC14") (pin "14") (pinfunction "~{DRDY}_14") (pintype "output"))
      (node (ref "JP2") (pin "3") (pinfunction "3_3") (pintype "passive"))
    )
    (net (code "159") (name "~{PS_RESET}") (class "Default")
      (node (ref "IC9") (pin "6") (pinfunction "~{RESET}_6") (pintype "input"))
      (node (ref "X3") (pin "5") (pinfunction "1_5") (pintype "passive"))
    )
    (net (code "160") (name "~{SET_100%}") (class "Default")
      (node (ref "IC9") (pin "13") (pinfunction "GP3_13") (pintype "bidirectional"))
      (node (ref "Q3") (pin "1") (pinfunction "G_1") (pintype "passive"))
    )
    (net (code "161") (name "~{SET_DP}") (class "Default")
      (node (ref "IC9") (pin "11") (pinfunction "GP1_11") (pintype "bidirectional"))
      (node (ref "Q14") (pin "1") (pinfunction "G_1") (pintype "passive"))
      (node (ref "R73") (pin "2") (pinfunction "2_2") (pintype "passive"))
    )
  )
)
